# Amplifier_Mixer.net
KiCad netlist of a schematic drawn in EAGLE
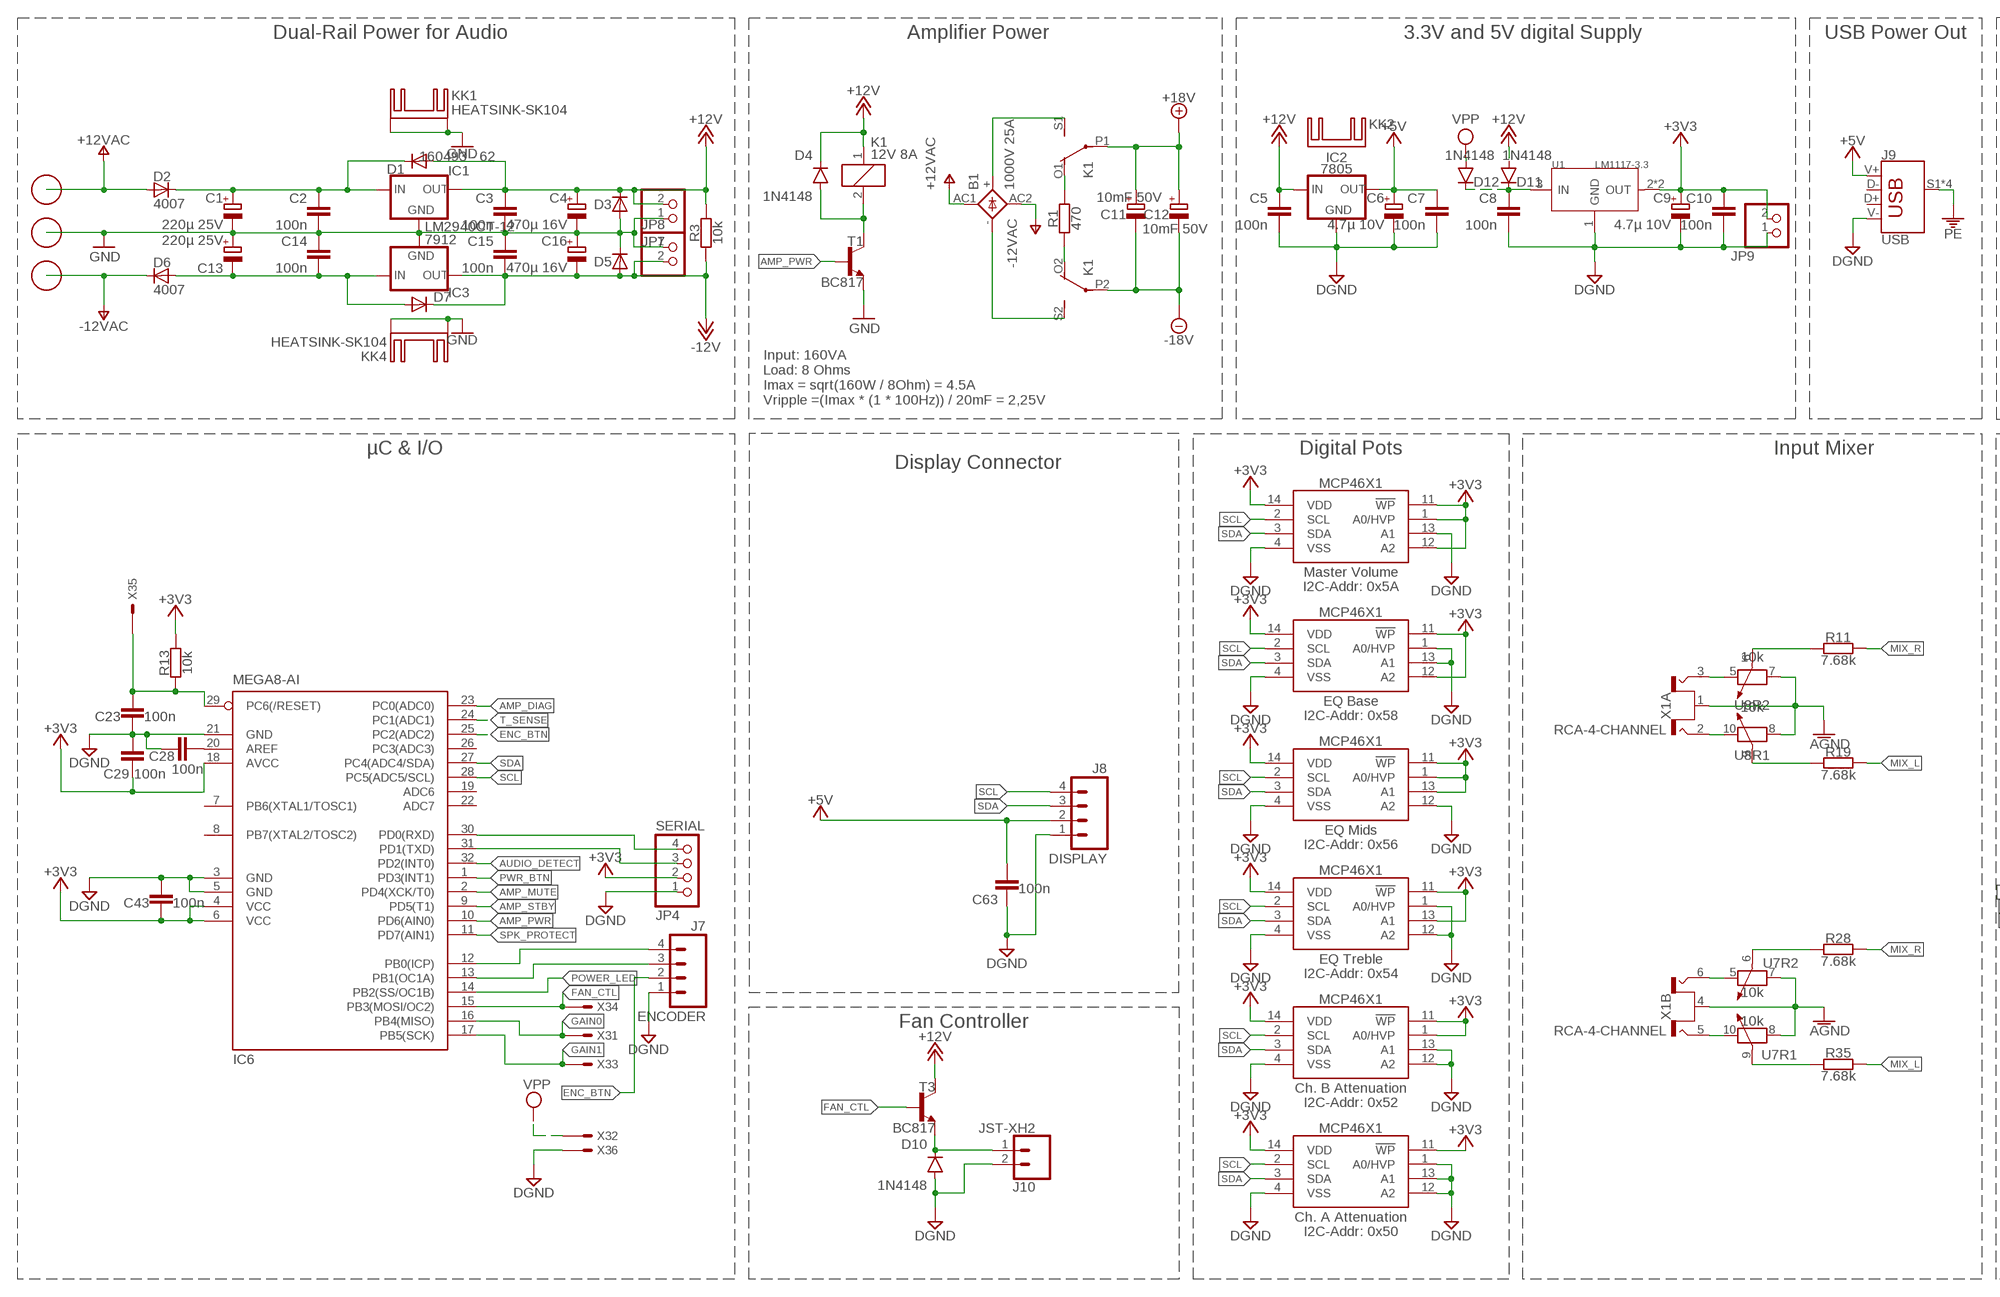
[diagram p0: schematic, sheet 1, part 1 of 2]
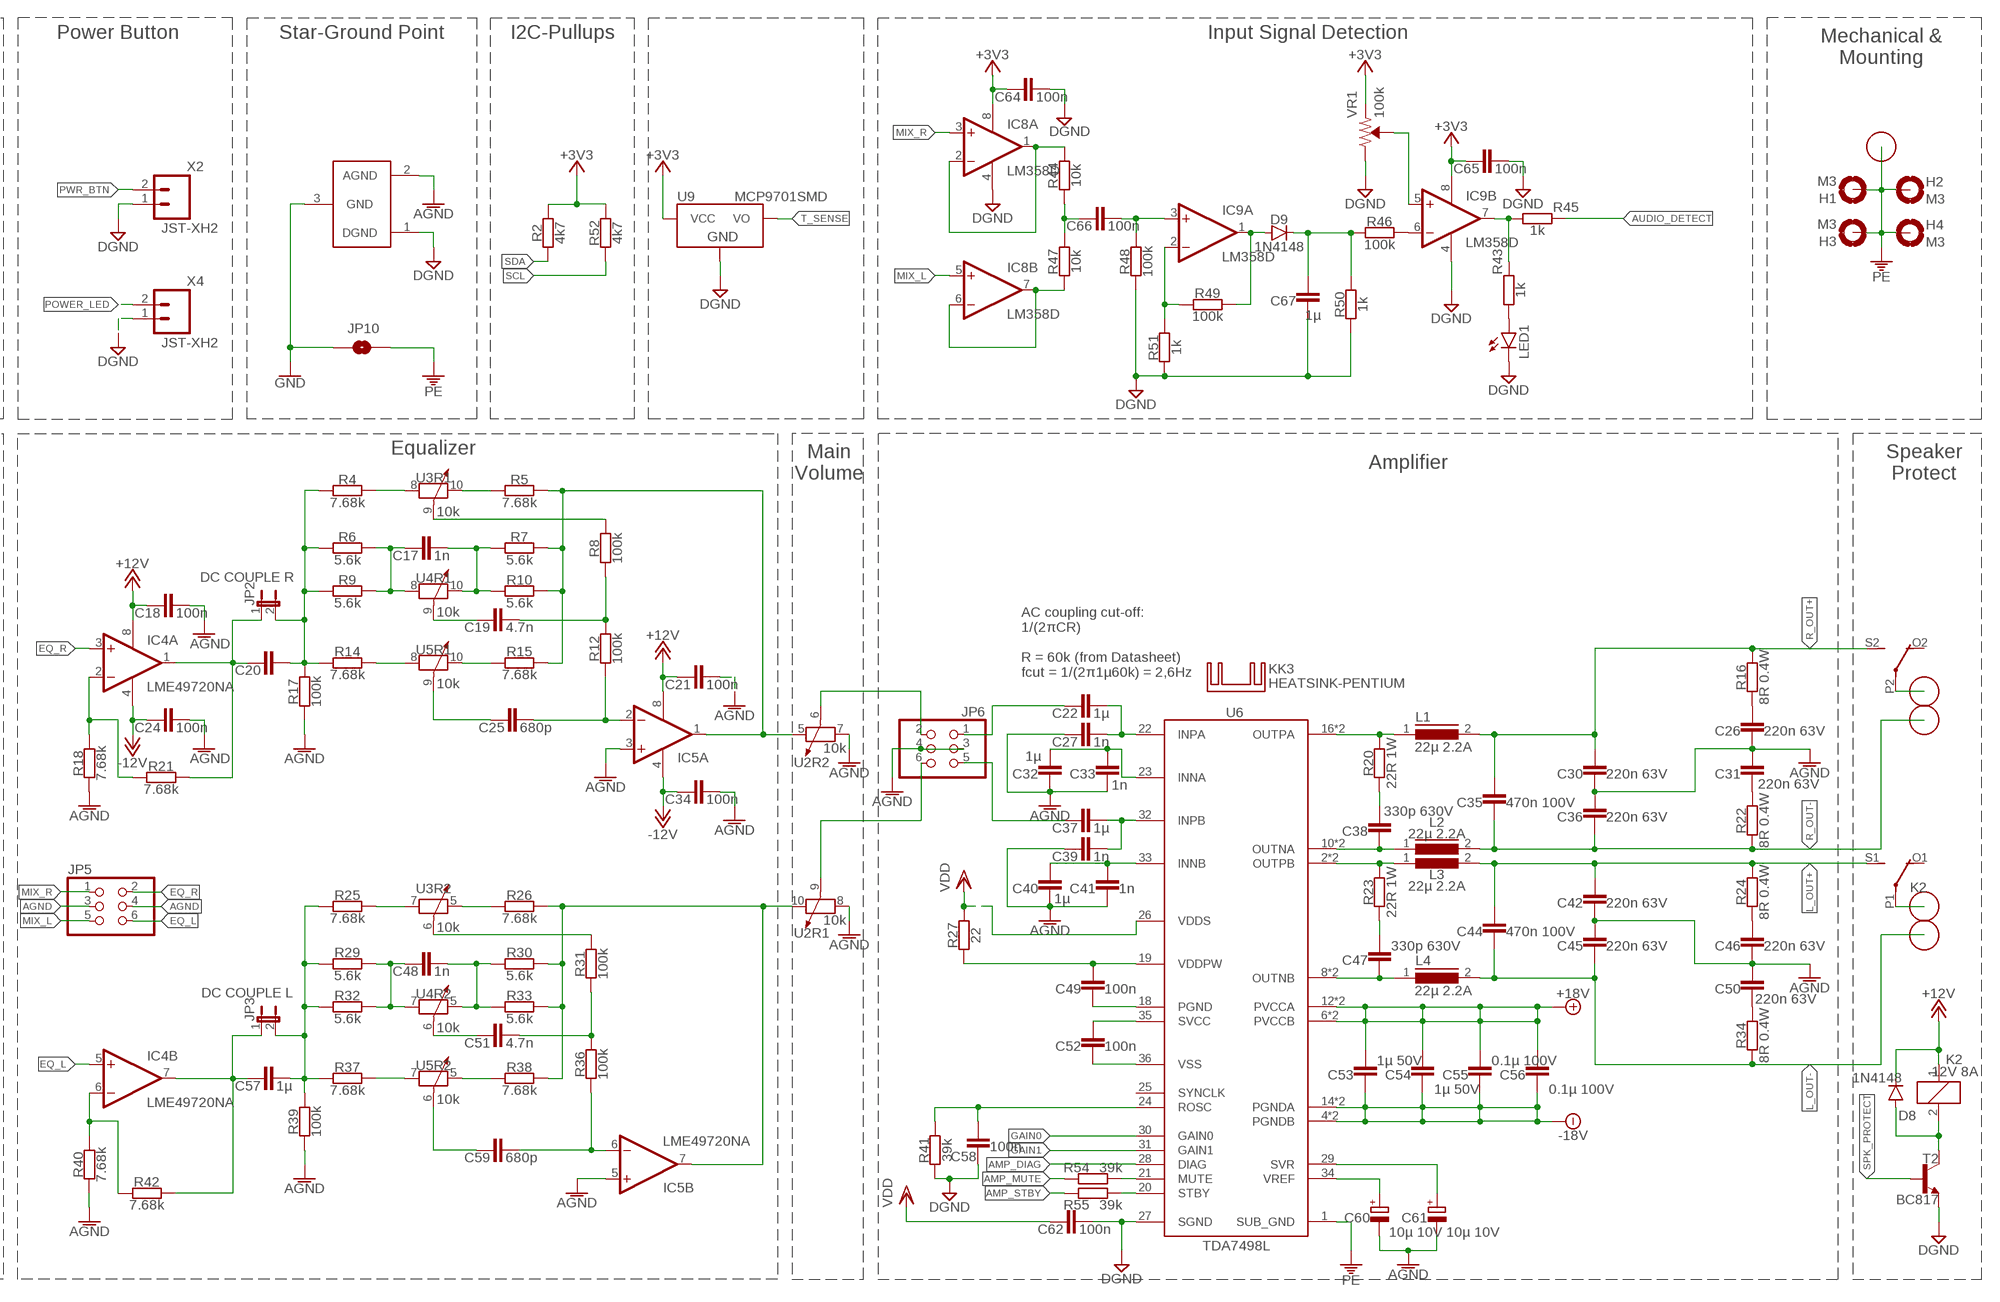
[diagram p1: schematic, sheet 1, part 2 of 2]

(export (version "E")
  (design (tool "Eeschema 10.0.6"))
  (components
    (comp (ref "B1")
      (value "1000V 25A")
      (footprint "eagle-import:FB100")
      (libsource (lib "eagle-import") (part "RECTIFIER-FB100"))
    )
    (comp (ref "C1")
      (value "220µ 25V")
      (footprint "eagle-import:175TMP-0810")
      (libsource (lib "eagle-import") (part "CPOL-EU175TMP-0810"))
    )
    (comp (ref "C2")
      (value "100n")
      (footprint "eagle-import:C0603")
      (libsource (lib "eagle-import") (part "C-EUC0603"))
    )
    (comp (ref "C3")
      (value "100n")
      (footprint "eagle-import:C0603")
      (libsource (lib "eagle-import") (part "C-EUC0603"))
    )
    (comp (ref "C4")
      (value "470µ 16V")
      (footprint "eagle-import:175TMP-0810")
      (libsource (lib "eagle-import") (part "CPOL-EU175TMP-0810"))
    )
    (comp (ref "C5")
      (value "100n")
      (footprint "eagle-import:C0603")
      (libsource (lib "eagle-import") (part "C-EUC0603"))
    )
    (comp (ref "C6")
      (value "4.7µ 10V")
      (footprint "eagle-import:153CLV-0505")
      (libsource (lib "eagle-import") (part "CPOL-EU153CLV-0505"))
    )
    (comp (ref "C7")
      (value "100n")
      (footprint "eagle-import:C0603")
      (libsource (lib "eagle-import") (part "C-EUC0603"))
    )
    (comp (ref "C8")
      (value "100n")
      (footprint "eagle-import:C0603")
      (libsource (lib "eagle-import") (part "C-EUC0603"))
    )
    (comp (ref "C9")
      (value "4.7µ 10V")
      (footprint "eagle-import:153CLV-0505")
      (libsource (lib "eagle-import") (part "CPOL-EU153CLV-0505"))
    )
    (comp (ref "C10")
      (value "100n")
      (footprint "eagle-import:C0603")
      (libsource (lib "eagle-import") (part "C-EUC0603"))
    )
    (comp (ref "C11")
      (value "10mF 50V")
      (footprint "eagle-import:EB35D")
      (libsource (lib "eagle-import") (part "TEAPO-SLG109M050S1A5T"))
    )
    (comp (ref "C12")
      (value "10mF 50V")
      (footprint "eagle-import:EB35D")
      (libsource (lib "eagle-import") (part "TEAPO-SLG109M050S1A5T"))
    )
    (comp (ref "C13")
      (value "220µ 25V")
      (footprint "eagle-import:175TMP-0810")
      (libsource (lib "eagle-import") (part "CPOL-EU175TMP-0810"))
    )
    (comp (ref "C14")
      (value "100n")
      (footprint "eagle-import:C0603")
      (libsource (lib "eagle-import") (part "C-EUC0603"))
    )
    (comp (ref "C15")
      (value "100n")
      (footprint "eagle-import:C0603")
      (libsource (lib "eagle-import") (part "C-EUC0603"))
    )
    (comp (ref "C16")
      (value "470µ 16V")
      (footprint "eagle-import:175TMP-0810")
      (libsource (lib "eagle-import") (part "CPOL-EU175TMP-0810"))
    )
    (comp (ref "C17")
      (value "1n")
      (footprint "eagle-import:C050-025X075")
      (libsource (lib "eagle-import") (part "C-EU050-025X075"))
    )
    (comp (ref "C18")
      (value "100n")
      (footprint "eagle-import:C0603")
      (libsource (lib "eagle-import") (part "C-EUC0603"))
    )
    (comp (ref "C19")
      (value "4.7n")
      (footprint "eagle-import:C075-032X103")
      (libsource (lib "eagle-import") (part "C-EU075-032X103"))
    )
    (comp (ref "C20")
      (value "DC COUPLE L")
      (footprint "eagle-import:C050-050X075")
      (libsource (lib "eagle-import") (part "C-EU050-050X075"))
    )
    (comp (ref "C21")
      (value "100n")
      (footprint "eagle-import:C0603")
      (libsource (lib "eagle-import") (part "C-EUC0603"))
    )
    (comp (ref "C22")
      (value "1µ")
      (footprint "eagle-import:C050-050X075")
      (libsource (lib "eagle-import") (part "C-EU050-050X075"))
    )
    (comp (ref "C23")
      (value "100n")
      (footprint "eagle-import:C0603")
      (libsource (lib "eagle-import") (part "C-EUC0603"))
    )
    (comp (ref "C24")
      (value "100n")
      (footprint "eagle-import:C0603")
      (libsource (lib "eagle-import") (part "C-EUC0603"))
    )
    (comp (ref "C25")
      (value "680p")
      (footprint "eagle-import:C050-045X075")
      (libsource (lib "eagle-import") (part "C-EU050-045X075"))
    )
    (comp (ref "C26")
      (value "220n 63V")
      (footprint "eagle-import:C050-025X075")
      (libsource (lib "eagle-import") (part "C-EU050-025X075"))
    )
    (comp (ref "C27")
      (value "1n")
      (footprint "eagle-import:C050-025X075")
      (libsource (lib "eagle-import") (part "C-EU050-025X075"))
    )
    (comp (ref "C28")
      (value "100n")
      (footprint "eagle-import:C0603")
      (libsource (lib "eagle-import") (part "C-EUC0603"))
    )
    (comp (ref "C29")
      (value "100n")
      (footprint "eagle-import:C0603")
      (libsource (lib "eagle-import") (part "C-EUC0603"))
    )
    (comp (ref "C30")
      (value "220n 63V")
      (footprint "eagle-import:C050-025X075")
      (libsource (lib "eagle-import") (part "C-EU050-025X075"))
    )
    (comp (ref "C31")
      (value "220n 63V")
      (footprint "eagle-import:C050-025X075")
      (libsource (lib "eagle-import") (part "C-EU050-025X075"))
    )
    (comp (ref "C32")
      (value "1µ")
      (footprint "eagle-import:C050-050X075")
      (libsource (lib "eagle-import") (part "C-EU050-050X075"))
    )
    (comp (ref "C33")
      (value "1n")
      (footprint "eagle-import:C050-025X075")
      (libsource (lib "eagle-import") (part "C-EU050-025X075"))
    )
    (comp (ref "C34")
      (value "100n")
      (footprint "eagle-import:C0603")
      (libsource (lib "eagle-import") (part "C-EUC0603"))
    )
    (comp (ref "C35")
      (value "470n 100V")
      (footprint "eagle-import:C050-045X075")
      (libsource (lib "eagle-import") (part "C-EU050-045X075"))
    )
    (comp (ref "C36")
      (value "220n 63V")
      (footprint "eagle-import:C050-025X075")
      (libsource (lib "eagle-import") (part "C-EU050-025X075"))
    )
    (comp (ref "C37")
      (value "1µ")
      (footprint "eagle-import:C050-050X075")
      (libsource (lib "eagle-import") (part "C-EU050-050X075"))
    )
    (comp (ref "C38")
      (value "330p 630V")
      (footprint "eagle-import:C050-045X075")
      (libsource (lib "eagle-import") (part "C-EU050-045X075"))
    )
    (comp (ref "C39")
      (value "1n")
      (footprint "eagle-import:C050-025X075")
      (libsource (lib "eagle-import") (part "C-EU050-025X075"))
    )
    (comp (ref "C40")
      (value "1µ")
      (footprint "eagle-import:C050-050X075")
      (libsource (lib "eagle-import") (part "C-EU050-050X075"))
    )
    (comp (ref "C41")
      (value "1n")
      (footprint "eagle-import:C050-025X075")
      (libsource (lib "eagle-import") (part "C-EU050-025X075"))
    )
    (comp (ref "C42")
      (value "220n 63V")
      (footprint "eagle-import:C050-025X075")
      (libsource (lib "eagle-import") (part "C-EU050-025X075"))
    )
    (comp (ref "C43")
      (value "100n")
      (footprint "eagle-import:C0603")
      (libsource (lib "eagle-import") (part "C-EUC0603"))
    )
    (comp (ref "C44")
      (value "470n 100V")
      (footprint "eagle-import:C050-045X075")
      (libsource (lib "eagle-import") (part "C-EU050-045X075"))
    )
    (comp (ref "C45")
      (value "220n 63V")
      (footprint "eagle-import:C050-025X075")
      (libsource (lib "eagle-import") (part "C-EU050-025X075"))
    )
    (comp (ref "C46")
      (value "220n 63V")
      (footprint "eagle-import:C050-025X075")
      (libsource (lib "eagle-import") (part "C-EU050-025X075"))
    )
    (comp (ref "C47")
      (value "330p 630V")
      (footprint "eagle-import:C050-045X075")
      (libsource (lib "eagle-import") (part "C-EU050-045X075"))
    )
    (comp (ref "C48")
      (value "1n")
      (footprint "eagle-import:C050-025X075")
      (libsource (lib "eagle-import") (part "C-EU050-025X075"))
    )
    (comp (ref "C49")
      (value "100n")
      (footprint "eagle-import:C0603")
      (libsource (lib "eagle-import") (part "C-EUC0603"))
    )
    (comp (ref "C50")
      (value "220n 63V")
      (footprint "eagle-import:C050-025X075")
      (libsource (lib "eagle-import") (part "C-EU050-025X075"))
    )
    (comp (ref "C51")
      (value "4.7n")
      (footprint "eagle-import:C075-032X103")
      (libsource (lib "eagle-import") (part "C-EU075-032X103"))
    )
    (comp (ref "C52")
      (value "100n")
      (footprint "eagle-import:C0603")
      (libsource (lib "eagle-import") (part "C-EUC0603"))
    )
    (comp (ref "C53")
      (value "1µ 50V")
      (footprint "eagle-import:C1206K")
      (fields (field (name "SPICEPREFIX") "Kemet C1206C105K5RAC7800+"))
      (libsource (lib "eagle-import") (part "C-EUC1206K"))
    )
    (comp (ref "C54")
      (value "1µ 50V")
      (footprint "eagle-import:C1206K")
      (fields (field (name "SPICEPREFIX") "Kemet C1206C105K5RAC7800+"))
      (libsource (lib "eagle-import") (part "C-EUC1206K"))
    )
    (comp (ref "C55")
      (value "0.1µ 100V")
      (footprint "eagle-import:C1206K")
      (fields (field (name "SPICEPREFIX") "Kemet C1206C104K1RAC7800+"))
      (libsource (lib "eagle-import") (part "C-EUC1206K"))
    )
    (comp (ref "C56")
      (value "0.1µ 100V")
      (footprint "eagle-import:C1206K")
      (fields (field (name "SPICEPREFIX") "Kemet C1206C104K1RAC7800+"))
      (libsource (lib "eagle-import") (part "C-EUC1206K"))
    )
    (comp (ref "C57")
      (value "1µ")
      (footprint "eagle-import:C050-050X075")
      (libsource (lib "eagle-import") (part "C-EU050-050X075"))
    )
    (comp (ref "C58")
      (value "100n")
      (footprint "eagle-import:C0603")
      (libsource (lib "eagle-import") (part "C-EUC0603"))
    )
    (comp (ref "C59")
      (value "680p")
      (footprint "eagle-import:C050-045X075")
      (libsource (lib "eagle-import") (part "C-EU050-045X075"))
    )
    (comp (ref "C60")
      (value "10µ 10V")
      (footprint "eagle-import:153CLV-0505")
      (libsource (lib "eagle-import") (part "CPOL-EU153CLV-0505"))
    )
    (comp (ref "C61")
      (value "10µ 10V")
      (footprint "eagle-import:153CLV-0505")
      (libsource (lib "eagle-import") (part "CPOL-EU153CLV-0505"))
    )
    (comp (ref "C62")
      (value "100n")
      (footprint "eagle-import:C0603")
      (libsource (lib "eagle-import") (part "C-EUC0603"))
    )
    (comp (ref "C63")
      (value "100n")
      (footprint "eagle-import:C0603")
      (libsource (lib "eagle-import") (part "C-EUC0603"))
    )
    (comp (ref "C64")
      (value "100n")
      (footprint "eagle-import:C0603")
      (libsource (lib "eagle-import") (part "C-EUC0603"))
    )
    (comp (ref "C65")
      (value "100n")
      (footprint "eagle-import:C0603")
      (libsource (lib "eagle-import") (part "C-EUC0603"))
    )
    (comp (ref "C66")
      (value "100n")
      (footprint "eagle-import:C0603")
      (libsource (lib "eagle-import") (part "C-EUC0603"))
    )
    (comp (ref "C67")
      (value "1µ")
      (footprint "eagle-import:C0603")
      (libsource (lib "eagle-import") (part "C-EUC0603"))
    )
    (comp (ref "D1")
      (value "4007")
      (footprint "eagle-import:SODFL5024X231")
      (fields (field (name "CONRAD") "160493 - 62"))
      (libsource (lib "eagle-import") (part "DIODE"))
    )
    (comp (ref "D2")
      (value "4007")
      (footprint "eagle-import:SODFL5024X231")
      (libsource (lib "eagle-import") (part "DIODE"))
    )
    (comp (ref "D3")
      (value "4007")
      (footprint "eagle-import:SODFL5024X231")
      (libsource (lib "eagle-import") (part "DIODE"))
    )
    (comp (ref "D4")
      (value "1N4148")
      (footprint "eagle-import:SOD-323")
      (libsource (lib "eagle-import") (part "DIODEBAS16"))
    )
    (comp (ref "D5")
      (value "4007")
      (footprint "eagle-import:SODFL5024X231")
      (libsource (lib "eagle-import") (part "DIODE"))
    )
    (comp (ref "D6")
      (value "4007")
      (footprint "eagle-import:SODFL5024X231")
      (libsource (lib "eagle-import") (part "DIODE"))
    )
    (comp (ref "D7")
      (value "4007")
      (footprint "eagle-import:SODFL5024X231")
      (libsource (lib "eagle-import") (part "DIODE"))
    )
    (comp (ref "D8")
      (value "1N4148")
      (footprint "eagle-import:SOD-323")
      (libsource (lib "eagle-import") (part "DIODEBAS16"))
    )
    (comp (ref "D9")
      (value "1N4148")
      (footprint "eagle-import:SOD-323")
      (libsource (lib "eagle-import") (part "DIODEBAS16"))
    )
    (comp (ref "D10")
      (value "1N4148")
      (footprint "eagle-import:SOD-323")
      (libsource (lib "eagle-import") (part "DIODEBAS16"))
    )
    (comp (ref "D11")
      (value "1N4148")
      (footprint "eagle-import:SOD-323")
      (libsource (lib "eagle-import") (part "DIODEBAS16"))
    )
    (comp (ref "D12")
      (value "1N4148")
      (footprint "eagle-import:SOD-323")
      (libsource (lib "eagle-import") (part "DIODEBAS16"))
    )
    (comp (ref "H1")
      (value "M3")
      (footprint "eagle-import:3,0-PAD")
      (libsource (lib "eagle-import") (part "HOLE-3MM-PAD"))
    )
    (comp (ref "H2")
      (value "M3")
      (footprint "eagle-import:3,0-PAD")
      (libsource (lib "eagle-import") (part "HOLE-3MM-PAD"))
    )
    (comp (ref "H3")
      (value "M3")
      (footprint "eagle-import:3,0-PAD")
      (libsource (lib "eagle-import") (part "HOLE-3MM-PAD"))
    )
    (comp (ref "H4")
      (value "M3")
      (footprint "eagle-import:3,0-PAD")
      (libsource (lib "eagle-import") (part "HOLE-3MM-PAD"))
    )
    (comp (ref "IC1")
      (value "LM2940CT-12")
      (footprint "eagle-import:78XXS")
      (libsource (lib "eagle-import") (part "78XXS"))
    )
    (comp (ref "IC2")
      (value "7805")
      (footprint "eagle-import:78XXS")
      (libsource (lib "eagle-import") (part "78XXS"))
    )
    (comp (ref "IC3")
      (value "7912")
      (footprint "eagle-import:79XXS")
      (libsource (lib "eagle-import") (part "79XXS"))
    )
    (comp (ref "IC4")
      (value "LME49720NA")
      (footprint "eagle-import:DIL08")
      (fields (field (name "CONRAD") "1010937 - 62") (field (name "STOCK") "0"))
      (libsource (lib "eagle-import") (part "LM358N"))
    )
    (comp (ref "IC5")
      (value "LME49720NA")
      (footprint "eagle-import:DIL08")
      (fields (field (name "CONRAD") "1010937 - 62") (field (name "STOCK") "0"))
      (libsource (lib "eagle-import") (part "LM358N"))
    )
    (comp (ref "IC6")
      (value "MEGA8-AI")
      (footprint "eagle-import:TQFP32-08")
      (fields (field (name "MPN") "ATMEGA8-16AU"))
      (libsource (lib "eagle-import") (part "MEGA8-AI"))
    )
    (comp (ref "IC8")
      (value "LM358D")
      (footprint "eagle-import:SO08")
      (fields
        (field (name "CONRAD") "1010764 - 62")
        (field (name "MOUSER") "511-LM358DT")
        (field (name "STOCK") "2")
      )
      (libsource (lib "eagle-import") (part "2AMP_P8+4D"))
    )
    (comp (ref "IC9")
      (value "LM358D")
      (footprint "eagle-import:SO08")
      (fields
        (field (name "CONRAD") "1010764 - 62")
        (field (name "MOUSER") "511-LM358DT")
        (field (name "STOCK") "2")
      )
      (libsource (lib "eagle-import") (part "2AMP_P8+4D"))
    )
    (comp (ref "J1")
      (value "6MM")
      (footprint "eagle-import:TE-726386")
      (libsource (lib "eagle-import") (part "TERMINAL-1"))
    )
    (comp (ref "J2")
      (value "6MM")
      (footprint "eagle-import:TE-726386")
      (libsource (lib "eagle-import") (part "TERMINAL-1"))
    )
    (comp (ref "J3")
      (value "6MM")
      (footprint "eagle-import:TE-726386")
      (libsource (lib "eagle-import") (part "TERMINAL-1"))
    )
    (comp (ref "J4")
      (value "6MM")
      (footprint "eagle-import:TE-726386")
      (libsource (lib "eagle-import") (part "TERMINAL-1"))
    )
    (comp (ref "J5")
      (value "TERMINAL-BLOCK-2PLUG-IN")
      (footprint "eagle-import:MSTBV2")
      (fields
        (field (name "CONRAD") "1327203 - 62")
        (field (name "MOUSER") "651-1954919")
        (field (name "STOCK") "2")
      )
      (libsource (lib "eagle-import") (part "TERMINAL-BLOCK-2PLUG-IN"))
    )
    (comp (ref "J6")
      (value "TERMINAL-BLOCK-2PLUG-IN")
      (footprint "eagle-import:MSTBV2")
      (fields
        (field (name "CONRAD") "1327203 - 62")
        (field (name "MOUSER") "651-1954919")
        (field (name "STOCK") "2")
      )
      (libsource (lib "eagle-import") (part "TERMINAL-BLOCK-2PLUG-IN"))
    )
    (comp (ref "J7")
      (value "ENCODER")
      (footprint "eagle-import:JST-4-PTH-VERT")
      (libsource (lib "eagle-import") (part "JST-XH4"))
    )
    (comp (ref "J8")
      (value "DISPLAY")
      (footprint "eagle-import:JST-4-PTH-VERT")
      (libsource (lib "eagle-import") (part "JST-XH4"))
    )
    (comp (ref "J9")
      (value "USB")
      (footprint "eagle-import:ECON-USBBUVA")
      (libsource (lib "eagle-import") (part "USB"))
    )
    (comp (ref "J10")
      (value "JST-XH2")
      (footprint "eagle-import:JST-2-PTH-VERT")
      (libsource (lib "eagle-import") (part "JST-XH2"))
    )
    (comp (ref "JP1")
      (value "GND_CONNECT")
      (footprint "eagle-import:GND_CONNECT")
      (libsource (lib "eagle-import") (part "GND_CONNECT"))
    )
    (comp (ref "JP2")
      (value "DC COULE R")
      (footprint "eagle-import:JP1")
      (libsource (lib "eagle-import") (part "JP1E"))
    )
    (comp (ref "JP3")
      (value "DC COUPLE L")
      (footprint "eagle-import:JP1")
      (libsource (lib "eagle-import") (part "JP1E"))
    )
    (comp (ref "JP4")
      (value "SERIAL")
      (footprint "eagle-import:1X04")
      (libsource (lib "eagle-import") (part "PINHD-1X4"))
    )
    (comp (ref "JP5")
      (value "MIX OUT")
      (footprint "eagle-import:2X03")
      (libsource (lib "eagle-import") (part "PINHD-2X3"))
    )
    (comp (ref "JP6")
      (value "PREAMP OUT")
      (footprint "eagle-import:2X03")
      (libsource (lib "eagle-import") (part "PINHD-2X3"))
    )
    (comp (ref "JP7")
      (value "PINHD-1X2")
      (footprint "eagle-import:1X02")
      (libsource (lib "eagle-import") (part "PINHD-1X2"))
    )
    (comp (ref "JP8")
      (value "PINHD-1X2")
      (footprint "eagle-import:1X02")
      (libsource (lib "eagle-import") (part "PINHD-1X2"))
    )
    (comp (ref "JP9")
      (value "PINHD-1X2")
      (footprint "eagle-import:1X02")
      (libsource (lib "eagle-import") (part "PINHD-1X2"))
    )
    (comp (ref "JP10")
      (value "PEGND")
      (footprint "eagle-import:SMT-JUMPER_2_NO_NO-SILK")
      (libsource (lib "eagle-import") (part "JUMPER-SMT_2_NO_NO-SILK"))
    )
    (comp (ref "K1")
      (value "12V 8A")
      (footprint "eagle-import:F4052")
      (fields
        (field (name "CONRAD") "629528 - 62")
        (field (name "MOUSER") "655-RT424012")
        (field (name "SPEC") "Hongfa HF115F/012-2ZS4A")
        (field (name "STOCK") "0")
      )
      (libsource (lib "eagle-import") (part "RELAY-F40.52"))
    )
    (comp (ref "K2")
      (value "12V 8A")
      (footprint "eagle-import:F4052")
      (fields
        (field (name "CONRAD") "629528 - 62")
        (field (name "SPEC") "Hongfa HF115F/012-2ZS4A")
        (field (name "MOUSER") "655-RT424012")
        (field (name "STOCK") "0")
      )
      (libsource (lib "eagle-import") (part "RELAY-F40.52"))
    )
    (comp (ref "KK1")
      (value "HEATSINK-SK104")
      (footprint "eagle-import:SK104-PAD")
      (libsource (lib "eagle-import") (part "HEATSINK-SK104"))
    )
    (comp (ref "KK2")
      (value "HEATSINK-SK95")
      (footprint "eagle-import:SK95-2M3")
      (libsource (lib "eagle-import") (part "HEATSINK-SK95"))
    )
    (comp (ref "KK3")
      (value "HEATSINK-PENTIUM")
      (footprint "eagle-import:HEATSINK-PENTIUM")
      (libsource (lib "eagle-import") (part "HEATSINK-PENTIUM"))
    )
    (comp (ref "KK4")
      (value "HEATSINK-SK104")
      (footprint "eagle-import:SK104-PAD")
      (libsource (lib "eagle-import") (part "HEATSINK-SK104"))
    )
    (comp (ref "L1")
      (value "22µ 2.2A")
      (footprint "eagle-import:INDUCTOR-12MM")
      (libsource (lib "eagle-import") (part "INDUCTOR12MM-SMD"))
    )
    (comp (ref "L2")
      (value "22µ 2.2A")
      (footprint "eagle-import:INDUCTOR-12MM")
      (libsource (lib "eagle-import") (part "INDUCTOR12MM-SMD"))
    )
    (comp (ref "L3")
      (value "22µ 2.2A")
      (footprint "eagle-import:INDUCTOR-12MM")
      (libsource (lib "eagle-import") (part "INDUCTOR12MM-SMD"))
    )
    (comp (ref "L4")
      (value "22µ 2.2A")
      (footprint "eagle-import:INDUCTOR-12MM")
      (libsource (lib "eagle-import") (part "INDUCTOR12MM-SMD"))
    )
    (comp (ref "LED1")
      (value "LEDCHIP-LED0603")
      (footprint "eagle-import:CHIP-LED0603")
      (libsource (lib "eagle-import") (part "LEDCHIP-LED0603"))
    )
    (comp (ref "R1")
      (value "470")
      (footprint "eagle-import:0617_22")
      (libsource (lib "eagle-import") (part "RESISTOR-0617-22"))
    )
    (comp (ref "R2")
      (value "4k7")
      (footprint "eagle-import:R0603")
      (libsource (lib "eagle-import") (part "R-EU_R0603"))
    )
    (comp (ref "R3")
      (value "10k")
      (footprint "eagle-import:R0603")
      (libsource (lib "eagle-import") (part "R-EU_R0603"))
    )
    (comp (ref "R4")
      (value "7.68k")
      (footprint "eagle-import:MINI_MELF-0207W")
      (libsource (lib "eagle-import") (part "R-EU_MELF0207W"))
    )
    (comp (ref "R5")
      (value "7.68k")
      (footprint "eagle-import:MINI_MELF-0207W")
      (libsource (lib "eagle-import") (part "R-EU_MELF0207W"))
    )
    (comp (ref "R6")
      (value "5.6k")
      (footprint "eagle-import:MINI_MELF-0207W")
      (libsource (lib "eagle-import") (part "R-EU_MELF0207W"))
    )
    (comp (ref "R7")
      (value "5.6k")
      (footprint "eagle-import:MINI_MELF-0207W")
      (libsource (lib "eagle-import") (part "R-EU_MELF0207W"))
    )
    (comp (ref "R8")
      (value "100k")
      (footprint "eagle-import:MINI_MELF-0204W")
      (libsource (lib "eagle-import") (part "R-EU_MELF0204W"))
    )
    (comp (ref "R9")
      (value "5.6k")
      (footprint "eagle-import:MINI_MELF-0207W")
      (libsource (lib "eagle-import") (part "R-EU_MELF0207W"))
    )
    (comp (ref "R10")
      (value "5.6k")
      (footprint "eagle-import:MINI_MELF-0207W")
      (libsource (lib "eagle-import") (part "R-EU_MELF0207W"))
    )
    (comp (ref "R11")
      (value "7.68k")
      (footprint "eagle-import:MINI_MELF-0207W")
      (libsource (lib "eagle-import") (part "R-EU_MELF0207W"))
    )
    (comp (ref "R12")
      (value "100k")
      (footprint "eagle-import:MINI_MELF-0204W")
      (libsource (lib "eagle-import") (part "R-EU_MELF0204W"))
    )
    (comp (ref "R13")
      (value "10k")
      (footprint "eagle-import:R0603")
      (libsource (lib "eagle-import") (part "R-EU_R0603"))
    )
    (comp (ref "R14")
      (value "7.68k")
      (footprint "eagle-import:MINI_MELF-0207W")
      (libsource (lib "eagle-import") (part "R-EU_MELF0207W"))
    )
    (comp (ref "R15")
      (value "7.68k")
      (footprint "eagle-import:MINI_MELF-0207W")
      (libsource (lib "eagle-import") (part "R-EU_MELF0207W"))
    )
    (comp (ref "R16")
      (value "8R 0.4W")
      (footprint "eagle-import:MINI_MELF-0204W")
      (libsource (lib "eagle-import") (part "R-EU_MELF0204W"))
    )
    (comp (ref "R17")
      (value "100k")
      (footprint "eagle-import:MINI_MELF-0204W")
      (libsource (lib "eagle-import") (part "R-EU_MELF0204W"))
    )
    (comp (ref "R18")
      (value "7.68k")
      (footprint "eagle-import:MINI_MELF-0207W")
      (libsource (lib "eagle-import") (part "R-EU_MELF0207W"))
    )
    (comp (ref "R19")
      (value "7.68k")
      (footprint "eagle-import:MINI_MELF-0207W")
      (libsource (lib "eagle-import") (part "R-EU_MELF0207W"))
    )
    (comp (ref "R20")
      (value "22R 1W")
      (footprint "eagle-import:MINI_MELF-0207W")
      (libsource (lib "eagle-import") (part "R-EU_MELF0207W"))
    )
    (comp (ref "R21")
      (value "7.68k")
      (footprint "eagle-import:MINI_MELF-0207W")
      (libsource (lib "eagle-import") (part "R-EU_MELF0207W"))
    )
    (comp (ref "R22")
      (value "8R 0.4W")
      (footprint "eagle-import:MINI_MELF-0204W")
      (libsource (lib "eagle-import") (part "R-EU_MELF0204W"))
    )
    (comp (ref "R23")
      (value "22R 1W")
      (footprint "eagle-import:MINI_MELF-0207W")
      (libsource (lib "eagle-import") (part "R-EU_MELF0207W"))
    )
    (comp (ref "R24")
      (value "8R 0.4W")
      (footprint "eagle-import:MINI_MELF-0204W")
      (libsource (lib "eagle-import") (part "R-EU_MELF0204W"))
    )
    (comp (ref "R25")
      (value "7.68k")
      (footprint "eagle-import:MINI_MELF-0207W")
      (libsource (lib "eagle-import") (part "R-EU_MELF0207W"))
    )
    (comp (ref "R26")
      (value "7.68k")
      (footprint "eagle-import:MINI_MELF-0207W")
      (libsource (lib "eagle-import") (part "R-EU_MELF0207W"))
    )
    (comp (ref "R27")
      (value "22")
      (footprint "eagle-import:R0603")
      (libsource (lib "eagle-import") (part "R-EU_R0603"))
    )
    (comp (ref "R28")
      (value "7.68k")
      (footprint "eagle-import:MINI_MELF-0207W")
      (libsource (lib "eagle-import") (part "R-EU_MELF0207W"))
    )
    (comp (ref "R29")
      (value "5.6k")
      (footprint "eagle-import:MINI_MELF-0207W")
      (libsource (lib "eagle-import") (part "R-EU_MELF0207W"))
    )
    (comp (ref "R30")
      (value "5.6k")
      (footprint "eagle-import:MINI_MELF-0207W")
      (libsource (lib "eagle-import") (part "R-EU_MELF0207W"))
    )
    (comp (ref "R31")
      (value "100k")
      (footprint "eagle-import:MINI_MELF-0204W")
      (libsource (lib "eagle-import") (part "R-EU_MELF0204W"))
    )
    (comp (ref "R32")
      (value "5.6k")
      (footprint "eagle-import:MINI_MELF-0207W")
      (libsource (lib "eagle-import") (part "R-EU_MELF0207W"))
    )
    (comp (ref "R33")
      (value "5.6k")
      (footprint "eagle-import:MINI_MELF-0207W")
      (libsource (lib "eagle-import") (part "R-EU_MELF0207W"))
    )
    (comp (ref "R34")
      (value "8R 0.4W")
      (footprint "eagle-import:MINI_MELF-0204W")
      (libsource (lib "eagle-import") (part "R-EU_MELF0204W"))
    )
    (comp (ref "R35")
      (value "7.68k")
      (footprint "eagle-import:MINI_MELF-0207W")
      (libsource (lib "eagle-import") (part "R-EU_MELF0207W"))
    )
    (comp (ref "R36")
      (value "100k")
      (footprint "eagle-import:MINI_MELF-0204W")
      (libsource (lib "eagle-import") (part "R-EU_MELF0204W"))
    )
    (comp (ref "R37")
      (value "7.68k")
      (footprint "eagle-import:MINI_MELF-0207W")
      (libsource (lib "eagle-import") (part "R-EU_MELF0207W"))
    )
    (comp (ref "R38")
      (value "7.68k")
      (footprint "eagle-import:MINI_MELF-0207W")
      (libsource (lib "eagle-import") (part "R-EU_MELF0207W"))
    )
    (comp (ref "R39")
      (value "100k")
      (footprint "eagle-import:MINI_MELF-0204W")
      (libsource (lib "eagle-import") (part "R-EU_MELF0204W"))
    )
    (comp (ref "R40")
      (value "7.68k")
      (footprint "eagle-import:MINI_MELF-0207W")
      (libsource (lib "eagle-import") (part "R-EU_MELF0207W"))
    )
    (comp (ref "R41")
      (value "39k")
      (footprint "eagle-import:R0603")
      (libsource (lib "eagle-import") (part "R-EU_R0603"))
    )
    (comp (ref "R42")
      (value "7.68k")
      (footprint "eagle-import:MINI_MELF-0207W")
      (libsource (lib "eagle-import") (part "R-EU_MELF0207W"))
    )
    (comp (ref "R43")
      (value "1k")
      (footprint "eagle-import:R0603")
      (libsource (lib "eagle-import") (part "R-EU_R0603"))
    )
    (comp (ref "R44")
      (value "10k")
      (footprint "eagle-import:R0603")
      (libsource (lib "eagle-import") (part "R-EU_R0603"))
    )
    (comp (ref "R45")
      (value "1k")
      (footprint "eagle-import:R0603")
      (libsource (lib "eagle-import") (part "R-EU_R0603"))
    )
    (comp (ref "R46")
      (value "100k")
      (footprint "eagle-import:R0603")
      (libsource (lib "eagle-import") (part "R-EU_R0603"))
    )
    (comp (ref "R47")
      (value "10k")
      (footprint "eagle-import:R0603")
      (libsource (lib "eagle-import") (part "R-EU_R0603"))
    )
    (comp (ref "R48")
      (value "100k")
      (footprint "eagle-import:R0603")
      (libsource (lib "eagle-import") (part "R-EU_R0603"))
    )
    (comp (ref "R49")
      (value "100k")
      (footprint "eagle-import:R0603")
      (libsource (lib "eagle-import") (part "R-EU_R0603"))
    )
    (comp (ref "R50")
      (value "1k")
      (footprint "eagle-import:R0603")
      (libsource (lib "eagle-import") (part "R-EU_R0603"))
    )
    (comp (ref "R51")
      (value "1k")
      (footprint "eagle-import:R0603")
      (libsource (lib "eagle-import") (part "R-EU_R0603"))
    )
    (comp (ref "R52")
      (value "4k7")
      (footprint "eagle-import:R0603")
      (libsource (lib "eagle-import") (part "R-EU_R0603"))
    )
    (comp (ref "R54")
      (value "39k")
      (footprint "eagle-import:R0603")
      (libsource (lib "eagle-import") (part "R-EU_R0603"))
    )
    (comp (ref "R55")
      (value "39k")
      (footprint "eagle-import:R0603")
      (libsource (lib "eagle-import") (part "R-EU_R0603"))
    )
    (comp (ref "T1")
      (value "BC817")
      (footprint "eagle-import:SOT23-BEC")
      (libsource (lib "eagle-import") (part "-NPN-SOT23-BECBC817-16"))
    )
    (comp (ref "T2")
      (value "BC817")
      (footprint "eagle-import:SOT23-BEC")
      (libsource (lib "eagle-import") (part "-NPN-SOT23-BECBC817-16"))
    )
    (comp (ref "T3")
      (value "BC817")
      (footprint "eagle-import:SOT23-BEC")
      (libsource (lib "eagle-import") (part "-NPN-SOT23-BECBC817-16"))
    )
    (comp (ref "U1")
      (value "LM1117-3.3")
      (footprint "eagle-import:SOT-223")
      (fields (field (name "MPN") "CJT1117-3.3"))
      (libsource (lib "eagle-import") (part "PMIC-CJT1117-3.3(SOT223)"))
    )
    (comp (ref "U2")
      (value "10k")
      (footprint "eagle-import:SOP65P640X120-14")
      (fields
        (field (name "CONRAD") "1083246 - 62")
        (field (name "MOUSER") "579-MCP4641-103E/ST")
        (field (name "STOCK") "6")
      )
      (libsource (lib "eagle-import") (part "MCP46X1"))
    )
    (comp (ref "U3")
      (value "10k")
      (footprint "eagle-import:SOP65P640X120-14")
      (fields
        (field (name "CONRAD") "1083246 - 62")
        (field (name "MOUSER") "579-MCP4641-103E/ST")
        (field (name "STOCK") "6")
      )
      (libsource (lib "eagle-import") (part "MCP46X1"))
    )
    (comp (ref "U4")
      (value "10k")
      (footprint "eagle-import:SOP65P640X120-14")
      (fields
        (field (name "CONRAD") "1083246 - 62")
        (field (name "MOUSER") "579-MCP4641-103E/ST")
        (field (name "STOCK") "6")
      )
      (libsource (lib "eagle-import") (part "MCP46X1"))
    )
    (comp (ref "U5")
      (value "10k")
      (footprint "eagle-import:SOP65P640X120-14")
      (fields
        (field (name "CONRAD") "1083246 - 62")
        (field (name "MOUSER") "579-MCP4641-103E/ST")
        (field (name "STOCK") "6")
      )
      (libsource (lib "eagle-import") (part "MCP46X1"))
    )
    (comp (ref "U6")
      (value "TDA7498L")
      (footprint "eagle-import:SOP50P1010X245-36")
      (libsource (lib "eagle-import") (part "TDA7498L"))
    )
    (comp (ref "U7")
      (value "10k")
      (footprint "eagle-import:SOP65P640X120-14")
      (fields
        (field (name "CONRAD") "1083246 - 62")
        (field (name "MOUSER") "579-MCP4641-103E/ST")
        (field (name "STOCK") "6")
      )
      (libsource (lib "eagle-import") (part "MCP46X1"))
    )
    (comp (ref "U8")
      (value "10k")
      (footprint "eagle-import:SOP65P640X120-14")
      (fields
        (field (name "CONRAD") "1083246 - 62")
        (field (name "MOUSER") "579-MCP4641-103E/ST")
        (field (name "STOCK") "6")
      )
      (libsource (lib "eagle-import") (part "MCP46X1"))
    )
    (comp (ref "U9")
      (value "MCP9701SMD")
      (footprint "eagle-import:SOT23-3")
      (libsource (lib "eagle-import") (part "MCP9700SMD"))
    )
    (comp (ref "VR1")
      (value "100k")
      (footprint "eagle-import:TRIMPOT-SMD-TC33X")
      (libsource (lib "eagle-import") (part "TRIMPOT-SMD-3MM-OPEN-1/10W-25%"))
    )
    (comp (ref "X1")
      (value "RCA-4-CHANNEL")
      (footprint "eagle-import:BKL-072385")
      (fields
        (field (name "CONRAD") "1578879 - 62")
        (field (name "MOUSER") "806-KLP42X-61-WWRR")
        (field (name "STOCK") "1")
      )
      (libsource (lib "eagle-import") (part "RCA-4-CHANNEL"))
    )
    (comp (ref "X2")
      (value "JST-XH2")
      (footprint "eagle-import:JST-2-PTH-VERT")
      (libsource (lib "eagle-import") (part "JST-XH2"))
    )
    (comp (ref "X3")
      (value "ICSP")
      (footprint "eagle-import:057-006-1")
      (fields
        (field (name "CONRAD") "1560967 - 62")
        (field (name "MOUSER") "200-TSW10307TD")
        (field (name "STOCK") "1")
      )
      (libsource (lib "eagle-import") (part "CONN-IDC-6"))
    )
    (comp (ref "X4")
      (value "JST-XH2")
      (footprint "eagle-import:JST-2-PTH-VERT")
      (libsource (lib "eagle-import") (part "JST-XH2"))
    )
  )
  (nets
    (net (code "1") (name "+3V3") (class "Default")
      (node (ref "C10") (pin "1") (pinfunction "1_1") (pintype "passive"))
      (node (ref "C29") (pin "1") (pinfunction "1_1") (pintype "passive"))
      (node (ref "C43") (pin "1") (pinfunction "1_1") (pintype "passive"))
      (node (ref "C64") (pin "1") (pinfunction "1_1") (pintype "passive"))
      (node (ref "C65") (pin "1") (pinfunction "1_1") (pintype "passive"))
      (node (ref "C9") (pin "+") (pinfunction "+_+") (pintype "passive"))
      (node (ref "IC6") (pin "18") (pinfunction "AVCC_18") (pintype "power_in"))
      (node (ref "IC6") (pin "4") (pinfunction "VCC_4") (pintype "power_in"))
      (node (ref "IC6") (pin "6") (pinfunction "VCC_6") (pintype "power_in"))
      (node (ref "IC8") (pin "8") (pinfunction "V+_8") (pintype "power_in"))
      (node (ref "IC9") (pin "8") (pinfunction "V+_8") (pintype "power_in"))
      (node (ref "JP4") (pin "2") (pinfunction "2_2") (pintype "passive"))
      (node (ref "JP9") (pin "2") (pinfunction "2_2") (pintype "passive"))
      (node (ref "R13") (pin "2") (pinfunction "2_2") (pintype "passive"))
      (node (ref "R2") (pin "2") (pinfunction "2_2") (pintype "passive"))
      (node (ref "R52") (pin "2") (pinfunction "2_2") (pintype "passive"))
      (node (ref "U1") (pin "2") (pinfunction "OUT_2") (pintype "bidirectional"))
      (node (ref "U1") (pin "TER") (pinfunction "OUT_TER") (pintype "bidirectional"))
      (node (ref "U2") (pin "1") (pinfunction "A0/HVP_1") (pintype "bidirectional"))
      (node (ref "U2") (pin "11") (pinfunction "~{WP}_11") (pintype "bidirectional"))
      (node (ref "U2") (pin "12") (pinfunction "A2_12") (pintype "bidirectional"))
      (node (ref "U2") (pin "14") (pinfunction "VDD_14") (pintype "bidirectional"))
      (node (ref "U3") (pin "11") (pinfunction "~{WP}_11") (pintype "bidirectional"))
      (node (ref "U3") (pin "12") (pinfunction "A2_12") (pintype "bidirectional"))
      (node (ref "U3") (pin "14") (pinfunction "VDD_14") (pintype "bidirectional"))
      (node (ref "U4") (pin "1") (pinfunction "A0/HVP_1") (pintype "bidirectional"))
      (node (ref "U4") (pin "11") (pinfunction "~{WP}_11") (pintype "bidirectional"))
      (node (ref "U4") (pin "13") (pinfunction "A1_13") (pintype "bidirectional"))
      (node (ref "U4") (pin "14") (pinfunction "VDD_14") (pintype "bidirectional"))
      (node (ref "U5") (pin "11") (pinfunction "~{WP}_11") (pintype "bidirectional"))
      (node (ref "U5") (pin "13") (pinfunction "A1_13") (pintype "bidirectional"))
      (node (ref "U5") (pin "14") (pinfunction "VDD_14") (pintype "bidirectional"))
      (node (ref "U7") (pin "1") (pinfunction "A0/HVP_1") (pintype "bidirectional"))
      (node (ref "U7") (pin "11") (pinfunction "~{WP}_11") (pintype "bidirectional"))
      (node (ref "U7") (pin "14") (pinfunction "VDD_14") (pintype "bidirectional"))
      (node (ref "U8") (pin "11") (pinfunction "~{WP}_11") (pintype "bidirectional"))
      (node (ref "U8") (pin "14") (pinfunction "VDD_14") (pintype "bidirectional"))
      (node (ref "U9") (pin "1") (pinfunction "VCC_1") (pintype "bidirectional"))
      (node (ref "VR1") (pin "3") (pinfunction "CCW_3") (pintype "passive"))
    )
    (net (code "2") (name "+5V") (class "Default")
      (node (ref "C6") (pin "+") (pinfunction "+_+") (pintype "passive"))
      (node (ref "C63") (pin "2") (pinfunction "2_2") (pintype "passive"))
      (node (ref "C7") (pin "1") (pinfunction "1_1") (pintype "passive"))
      (node (ref "IC2") (pin "OUT") (pinfunction "OUT_OUT") (pintype "passive"))
      (node (ref "J8") (pin "2") (pinfunction "2_2") (pintype "passive"))
      (node (ref "J9") (pin "V+") (pinfunction "VBUS_V+") (pintype "power_in"))
    )
    (net (code "3") (name "+12V") (class "Default")
      (node (ref "C18") (pin "1") (pinfunction "1_1") (pintype "passive"))
      (node (ref "C21") (pin "1") (pinfunction "1_1") (pintype "passive"))
      (node (ref "C3") (pin "1") (pinfunction "1_1") (pintype "passive"))
      (node (ref "C4") (pin "+") (pinfunction "+_+") (pintype "passive"))
      (node (ref "C5") (pin "1") (pinfunction "1_1") (pintype "passive"))
      (node (ref "D1") (pin "A") (pinfunction "A_A") (pintype "passive"))
      (node (ref "D11") (pin "A") (pinfunction "A_A") (pintype "passive"))
      (node (ref "D3") (pin "C") (pinfunction "C_C") (pintype "passive"))
      (node (ref "D4") (pin "C") (pinfunction "C_C") (pintype "passive"))
      (node (ref "D8") (pin "C") (pinfunction "C_C") (pintype "passive"))
      (node (ref "IC1") (pin "OUT") (pinfunction "OUT_OUT") (pintype "passive"))
      (node (ref "IC2") (pin "IN") (pinfunction "IN_IN") (pintype "input"))
      (node (ref "IC4") (pin "8") (pinfunction "V+_8") (pintype "power_in"))
      (node (ref "IC5") (pin "8") (pinfunction "V+_8") (pintype "power_in"))
      (node (ref "JP7") (pin "2") (pinfunction "2_2") (pintype "passive"))
      (node (ref "K1") (pin "1") (pinfunction "1_1") (pintype "passive"))
      (node (ref "K2") (pin "1") (pinfunction "1_1") (pintype "passive"))
      (node (ref "R3") (pin "1") (pinfunction "1_1") (pintype "passive"))
      (node (ref "T3") (pin "C") (pinfunction "C_C") (pintype "passive"))
    )
    (net (code "4") (name "+12VAC") (class "Default")
      (node (ref "B1") (pin "AC1") (pinfunction "AC1_AC1") (pintype "passive"))
      (node (ref "D2") (pin "A") (pinfunction "A_A") (pintype "passive"))
      (node (ref "J1") (pin "P$1") (pinfunction "P$1_P$1") (pintype "bidirectional"))
      (node (ref "J1") (pin "P$2") (pinfunction "P$1_P$2") (pintype "bidirectional"))
    )
    (net (code "5") (name "+18V") (class "Default")
      (node (ref "C11") (pin "+") (pinfunction "+_+") (pintype "passive"))
      (node (ref "C12") (pin "+") (pinfunction "+_+") (pintype "passive"))
      (node (ref "C53") (pin "1") (pinfunction "1_1") (pintype "passive"))
      (node (ref "C54") (pin "1") (pinfunction "1_1") (pintype "passive"))
      (node (ref "C55") (pin "1") (pinfunction "1_1") (pintype "passive"))
      (node (ref "C56") (pin "1") (pinfunction "1_1") (pintype "passive"))
      (node (ref "K1") (pin "P1") (pinfunction "P_P1") (pintype "passive"))
      (node (ref "U6") (pin "12") (pinfunction "PVCCA_12") (pintype "bidirectional"))
      (node (ref "U6") (pin "13") (pinfunction "PVCCA_13") (pintype "bidirectional"))
      (node (ref "U6") (pin "6") (pinfunction "PVCCB_6") (pintype "bidirectional"))
      (node (ref "U6") (pin "7") (pinfunction "PVCCB_7") (pintype "bidirectional"))
    )
    (net (code "6") (name "-12V") (class "Default")
      (node (ref "C15") (pin "2") (pinfunction "2_2") (pintype "passive"))
      (node (ref "C16") (pin "-") (pinfunction "-_-") (pintype "passive"))
      (node (ref "C24") (pin "1") (pinfunction "1_1") (pintype "passive"))
      (node (ref "C34") (pin "1") (pinfunction "1_1") (pintype "passive"))
      (node (ref "D5") (pin "A") (pinfunction "A_A") (pintype "passive"))
      (node (ref "D7") (pin "C") (pinfunction "C_C") (pintype "passive"))
      (node (ref "IC3") (pin "OUT") (pinfunction "OUT_OUT") (pintype "passive"))
      (node (ref "IC4") (pin "4") (pinfunction "V-_4") (pintype "power_in"))
      (node (ref "IC5") (pin "4") (pinfunction "V-_4") (pintype "power_in"))
      (node (ref "JP8") (pin "2") (pinfunction "2_2") (pintype "passive"))
      (node (ref "R3") (pin "2") (pinfunction "2_2") (pintype "passive"))
    )
    (net (code "7") (name "-12VAC") (class "Default")
      (node (ref "B1") (pin "AC2") (pinfunction "AC2_AC2") (pintype "passive"))
      (node (ref "D6") (pin "C") (pinfunction "C_C") (pintype "passive"))
      (node (ref "J3") (pin "P$1") (pinfunction "P$1_P$1") (pintype "bidirectional"))
      (node (ref "J3") (pin "P$2") (pinfunction "P$1_P$2") (pintype "bidirectional"))
    )
    (net (code "8") (name "-18V") (class "Default")
      (node (ref "C11") (pin "-") (pinfunction "-_-") (pintype "passive"))
      (node (ref "C12") (pin "-") (pinfunction "-_-") (pintype "passive"))
      (node (ref "C53") (pin "2") (pinfunction "2_2") (pintype "passive"))
      (node (ref "C54") (pin "2") (pinfunction "2_2") (pintype "passive"))
      (node (ref "C55") (pin "2") (pinfunction "2_2") (pintype "passive"))
      (node (ref "C56") (pin "2") (pinfunction "2_2") (pintype "passive"))
      (node (ref "K1") (pin "P2") (pinfunction "P_P2") (pintype "passive"))
      (node (ref "U6") (pin "14") (pinfunction "PGNDA_14") (pintype "bidirectional"))
      (node (ref "U6") (pin "15") (pinfunction "PGNDA_15") (pintype "bidirectional"))
      (node (ref "U6") (pin "4") (pinfunction "PGNDB_4") (pintype "bidirectional"))
      (node (ref "U6") (pin "5") (pinfunction "PGNDB_5") (pintype "bidirectional"))
    )
    (net (code "9") (name "AGND") (class "Default")
      (node (ref "C18") (pin "2") (pinfunction "2_2") (pintype "passive"))
      (node (ref "C21") (pin "2") (pinfunction "2_2") (pintype "passive"))
      (node (ref "C24") (pin "2") (pinfunction "2_2") (pintype "passive"))
      (node (ref "C26") (pin "2") (pinfunction "2_2") (pintype "passive"))
      (node (ref "C27") (pin "1") (pinfunction "1_1") (pintype "passive"))
      (node (ref "C30") (pin "2") (pinfunction "2_2") (pintype "passive"))
      (node (ref "C31") (pin "1") (pinfunction "1_1") (pintype "passive"))
      (node (ref "C32") (pin "1") (pinfunction "1_1") (pintype "passive"))
      (node (ref "C33") (pin "1") (pinfunction "1_1") (pintype "passive"))
      (node (ref "C34") (pin "2") (pinfunction "2_2") (pintype "passive"))
      (node (ref "C36") (pin "1") (pinfunction "1_1") (pintype "passive"))
      (node (ref "C39") (pin "1") (pinfunction "1_1") (pintype "passive"))
      (node (ref "C40") (pin "1") (pinfunction "1_1") (pintype "passive"))
      (node (ref "C41") (pin "1") (pinfunction "1_1") (pintype "passive"))
      (node (ref "C42") (pin "2") (pinfunction "2_2") (pintype "passive"))
      (node (ref "C45") (pin "1") (pinfunction "1_1") (pintype "passive"))
      (node (ref "C46") (pin "2") (pinfunction "2_2") (pintype "passive"))
      (node (ref "C50") (pin "1") (pinfunction "1_1") (pintype "passive"))
      (node (ref "C60") (pin "-") (pinfunction "-_-") (pintype "passive"))
      (node (ref "C61") (pin "-") (pinfunction "-_-") (pintype "passive"))
      (node (ref "IC5") (pin "3") (pinfunction "+IN_3") (pintype "input"))
      (node (ref "IC5") (pin "5") (pinfunction "+IN_5") (pintype "input"))
      (node (ref "JP1") (pin "2") (pinfunction "AGND_2") (pintype "bidirectional"))
      (node (ref "JP5") (pin "3") (pinfunction "3_3") (pintype "passive"))
      (node (ref "JP5") (pin "4") (pinfunction "4_4") (pintype "passive"))
      (node (ref "JP6") (pin "3") (pinfunction "3_3") (pintype "passive"))
      (node (ref "JP6") (pin "4") (pinfunction "4_4") (pintype "passive"))
      (node (ref "R17") (pin "1") (pinfunction "1_1") (pintype "passive"))
      (node (ref "R18") (pin "2") (pinfunction "2_2") (pintype "passive"))
      (node (ref "R39") (pin "1") (pinfunction "1_1") (pintype "passive"))
      (node (ref "R40") (pin "2") (pinfunction "2_2") (pintype "passive"))
      (node (ref "U2") (pin "7") (pinfunction "A_7") (pintype "passive"))
      (node (ref "U2") (pin "8") (pinfunction "A_8") (pintype "passive"))
      (node (ref "U7") (pin "7") (pinfunction "A_7") (pintype "passive"))
      (node (ref "U7") (pin "8") (pinfunction "A_8") (pintype "passive"))
      (node (ref "U8") (pin "7") (pinfunction "A_7") (pintype "passive"))
      (node (ref "U8") (pin "8") (pinfunction "A_8") (pintype "passive"))
      (node (ref "X1") (pin "1") (pinfunction "S_1") (pintype "passive"))
      (node (ref "X1") (pin "4") (pinfunction "S_4") (pintype "passive"))
    )
    (net (code "10") (name "AMP_DIAG") (class "Default")
      (node (ref "IC6") (pin "23") (pinfunction "PC0(ADC0)_23") (pintype "bidirectional"))
      (node (ref "U6") (pin "28") (pinfunction "DIAG_28") (pintype "bidirectional"))
    )
    (net (code "11") (name "AMP_MUTE") (class "Default")
      (node (ref "IC6") (pin "2") (pinfunction "PD4(XCK/T0)_2") (pintype "bidirectional"))
      (node (ref "R54") (pin "2") (pinfunction "2_2") (pintype "passive"))
    )
    (net (code "12") (name "AMP_PWR") (class "Default")
      (node (ref "IC6") (pin "10") (pinfunction "PD6(AIN0)_10") (pintype "bidirectional"))
      (node (ref "T1") (pin "B") (pinfunction "B_B") (pintype "passive"))
    )
    (net (code "13") (name "AMP_STBY") (class "Default")
      (node (ref "IC6") (pin "9") (pinfunction "PD5(T1)_9") (pintype "bidirectional"))
      (node (ref "R55") (pin "2") (pinfunction "2_2") (pintype "passive"))
    )
    (net (code "14") (name "AUDIO_DETECT") (class "Default")
      (node (ref "IC6") (pin "32") (pinfunction "PD2(INT0)_32") (pintype "bidirectional"))
      (node (ref "R45") (pin "1") (pinfunction "1_1") (pintype "passive"))
    )
    (net (code "15") (name "DGND") (class "Default")
      (node (ref "C10") (pin "2") (pinfunction "2_2") (pintype "passive"))
      (node (ref "C23") (pin "1") (pinfunction "1_1") (pintype "passive"))
      (node (ref "C28") (pin "2") (pinfunction "2_2") (pintype "passive"))
      (node (ref "C29") (pin "2") (pinfunction "2_2") (pintype "passive"))
      (node (ref "C43") (pin "2") (pinfunction "2_2") (pintype "passive"))
      (node (ref "C5") (pin "2") (pinfunction "2_2") (pintype "passive"))
      (node (ref "C58") (pin "2") (pinfunction "2_2") (pintype "passive"))
      (node (ref "C6") (pin "-") (pinfunction "-_-") (pintype "passive"))
      (node (ref "C62") (pin "1") (pinfunction "1_1") (pintype "passive"))
      (node (ref "C63") (pin "1") (pinfunction "1_1") (pintype "passive"))
      (node (ref "C64") (pin "2") (pinfunction "2_2") (pintype "passive"))
      (node (ref "C65") (pin "2") (pinfunction "2_2") (pintype "passive"))
      (node (ref "C67") (pin "1") (pinfunction "1_1") (pintype "passive"))
      (node (ref "C7") (pin "2") (pinfunction "2_2") (pintype "passive"))
      (node (ref "C8") (pin "2") (pinfunction "2_2") (pintype "passive"))
      (node (ref "C9") (pin "-") (pinfunction "-_-") (pintype "passive"))
      (node (ref "D10") (pin "A") (pinfunction "A_A") (pintype "passive"))
      (node (ref "IC2") (pin "GND") (pinfunction "GND_GND") (pintype "input"))
      (node (ref "IC6") (pin "21") (pinfunction "GND_21") (pintype "power_in"))
      (node (ref "IC6") (pin "3") (pinfunction "GND_3") (pintype "power_in"))
      (node (ref "IC6") (pin "5") (pinfunction "GND_5") (pintype "power_in"))
      (node (ref "IC8") (pin "4") (pinfunction "V-_4") (pintype "power_in"))
      (node (ref "IC9") (pin "4") (pinfunction "V-_4") (pintype "power_in"))
      (node (ref "J10") (pin "2") (pinfunction "2_2") (pintype "passive"))
      (node (ref "J7") (pin "1") (pinfunction "1_1") (pintype "passive"))
      (node (ref "J8") (pin "1") (pinfunction "1_1") (pintype "passive"))
      (node (ref "J9") (pin "V-") (pinfunction "GND_V-") (pintype "power_in"))
      (node (ref "JP1") (pin "1") (pinfunction "DGND_1") (pintype "bidirectional"))
      (node (ref "JP4") (pin "1") (pinfunction "1_1") (pintype "passive"))
      (node (ref "JP9") (pin "1") (pinfunction "1_1") (pintype "passive"))
      (node (ref "LED1") (pin "C") (pinfunction "C_C") (pintype "passive"))
      (node (ref "R41") (pin "1") (pinfunction "1_1") (pintype "passive"))
      (node (ref "R48") (pin "1") (pinfunction "1_1") (pintype "passive"))
      (node (ref "R50") (pin "1") (pinfunction "1_1") (pintype "passive"))
      (node (ref "R51") (pin "1") (pinfunction "1_1") (pintype "passive"))
      (node (ref "T2") (pin "E") (pinfunction "E_E") (pintype "passive"))
      (node (ref "U1") (pin "1") (pinfunction "GND_1") (pintype "bidirectional"))
      (node (ref "U2") (pin "13") (pinfunction "A1_13") (pintype "bidirectional"))
      (node (ref "U2") (pin "4") (pinfunction "VSS_4") (pintype "bidirectional"))
      (node (ref "U3") (pin "1") (pinfunction "A0/HVP_1") (pintype "bidirectional"))
      (node (ref "U3") (pin "13") (pinfunction "A1_13") (pintype "bidirectional"))
      (node (ref "U3") (pin "4") (pinfunction "VSS_4") (pintype "bidirectional"))
      (node (ref "U4") (pin "12") (pinfunction "A2_12") (pintype "bidirectional"))
      (node (ref "U4") (pin "4") (pinfunction "VSS_4") (pintype "bidirectional"))
      (node (ref "U5") (pin "1") (pinfunction "A0/HVP_1") (pintype "bidirectional"))
      (node (ref "U5") (pin "12") (pinfunction "A2_12") (pintype "bidirectional"))
      (node (ref "U5") (pin "4") (pinfunction "VSS_4") (pintype "bidirectional"))
      (node (ref "U6") (pin "27") (pinfunction "SGND_27") (pintype "bidirectional"))
      (node (ref "U7") (pin "12") (pinfunction "A2_12") (pintype "bidirectional"))
      (node (ref "U7") (pin "13") (pinfunction "A1_13") (pintype "bidirectional"))
      (node (ref "U7") (pin "4") (pinfunction "VSS_4") (pintype "bidirectional"))
      (node (ref "U8") (pin "1") (pinfunction "A0/HVP_1") (pintype "bidirectional"))
      (node (ref "U8") (pin "12") (pinfunction "A2_12") (pintype "bidirectional"))
      (node (ref "U8") (pin "13") (pinfunction "A1_13") (pintype "bidirectional"))
      (node (ref "U8") (pin "4") (pinfunction "VSS_4") (pintype "bidirectional"))
      (node (ref "U9") (pin "3") (pinfunction "GND_3") (pintype "bidirectional"))
      (node (ref "VR1") (pin "1") (pinfunction "CW_1") (pintype "passive"))
      (node (ref "X2") (pin "1") (pinfunction "1_1") (pintype "passive"))
      (node (ref "X3") (pin "6") (pinfunction "S_6") (pintype "passive"))
      (node (ref "X4") (pin "1") (pinfunction "1_1") (pintype "passive"))
    )
    (net (code "16") (name "ENC_BTN") (class "Default")
      (node (ref "IC6") (pin "25") (pinfunction "PC2(ADC2)_25") (pintype "bidirectional"))
      (node (ref "J7") (pin "2") (pinfunction "2_2") (pintype "passive"))
    )
    (net (code "17") (name "EQ_L") (class "Default")
      (node (ref "IC4") (pin "5") (pinfunction "+IN_5") (pintype "input"))
      (node (ref "JP5") (pin "6") (pinfunction "6_6") (pintype "passive"))
    )
    (net (code "18") (name "EQ_R") (class "Default")
      (node (ref "IC4") (pin "3") (pinfunction "+IN_3") (pintype "input"))
      (node (ref "JP5") (pin "2") (pinfunction "2_2") (pintype "passive"))
    )
    (net (code "19") (name "FAN_CTL") (class "Default")
      (node (ref "IC6") (pin "15") (pinfunction "PB3(MOSI/OC2)_15") (pintype "bidirectional"))
      (node (ref "T3") (pin "B") (pinfunction "B_B") (pintype "passive"))
      (node (ref "X3") (pin "4") (pinfunction "S_4") (pintype "passive"))
    )
    (net (code "20") (name "GAIN0") (class "Default")
      (node (ref "IC6") (pin "16") (pinfunction "PB4(MISO)_16") (pintype "bidirectional"))
      (node (ref "U6") (pin "30") (pinfunction "GAIN0_30") (pintype "bidirectional"))
      (node (ref "X3") (pin "1") (pinfunction "S_1") (pintype "passive"))
    )
    (net (code "21") (name "GAIN1") (class "Default")
      (node (ref "IC6") (pin "17") (pinfunction "PB5(SCK)_17") (pintype "bidirectional"))
      (node (ref "U6") (pin "31") (pinfunction "GAIN1_31") (pintype "bidirectional"))
      (node (ref "X3") (pin "3") (pinfunction "S_3") (pintype "passive"))
    )
    (net (code "22") (name "GND") (class "Default")
      (node (ref "C1") (pin "-") (pinfunction "-_-") (pintype "passive"))
      (node (ref "C13") (pin "+") (pinfunction "+_+") (pintype "passive"))
      (node (ref "C14") (pin "1") (pinfunction "1_1") (pintype "passive"))
      (node (ref "C15") (pin "1") (pinfunction "1_1") (pintype "passive"))
      (node (ref "C16") (pin "+") (pinfunction "+_+") (pintype "passive"))
      (node (ref "C2") (pin "2") (pinfunction "2_2") (pintype "passive"))
      (node (ref "C3") (pin "2") (pinfunction "2_2") (pintype "passive"))
      (node (ref "C4") (pin "-") (pinfunction "-_-") (pintype "passive"))
      (node (ref "D3") (pin "A") (pinfunction "A_A") (pintype "passive"))
      (node (ref "D5") (pin "C") (pinfunction "C_C") (pintype "passive"))
      (node (ref "IC1") (pin "GND") (pinfunction "GND_GND") (pintype "input"))
      (node (ref "IC3") (pin "GND") (pinfunction "GND_GND") (pintype "input"))
      (node (ref "J2") (pin "P$1") (pinfunction "P$1_P$1") (pintype "bidirectional"))
      (node (ref "J2") (pin "P$2") (pinfunction "P$1_P$2") (pintype "bidirectional"))
      (node (ref "JP1") (pin "3") (pinfunction "GND_3") (pintype "bidirectional"))
      (node (ref "JP10") (pin "1") (pinfunction "1_1") (pintype "passive"))
      (node (ref "JP7") (pin "1") (pinfunction "1_1") (pintype "passive"))
      (node (ref "JP8") (pin "1") (pinfunction "1_1") (pintype "passive"))
      (node (ref "KK1") (pin "K1") (pinfunction "K_K1") (pintype "passive"))
      (node (ref "KK1") (pin "K2") (pinfunction "K_K2") (pintype "passive"))
      (node (ref "KK4") (pin "K1") (pinfunction "K_K1") (pintype "passive"))
      (node (ref "KK4") (pin "K2") (pinfunction "K_K2") (pintype "passive"))
      (node (ref "T1") (pin "E") (pinfunction "E_E") (pintype "passive"))
    )
    (net (code "23") (name "L_OUT+") (class "Default")
      (node (ref "C42") (pin "1") (pinfunction "1_1") (pintype "passive"))
      (node (ref "C44") (pin "1") (pinfunction "1_1") (pintype "passive"))
      (node (ref "K2") (pin "S1") (pinfunction "S_S1") (pintype "passive"))
      (node (ref "L3") (pin "2") (pinfunction "2_2") (pintype "passive"))
      (node (ref "R24") (pin "2") (pinfunction "2_2") (pintype "passive"))
    )
    (net (code "24") (name "L_OUT-") (class "Default")
      (node (ref "C44") (pin "2") (pinfunction "2_2") (pintype "passive"))
      (node (ref "C45") (pin "2") (pinfunction "2_2") (pintype "passive"))
      (node (ref "J6") (pin "1") (pinfunction "P$1_1") (pintype "bidirectional"))
      (node (ref "L4") (pin "2") (pinfunction "2_2") (pintype "passive"))
      (node (ref "R34") (pin "1") (pinfunction "1_1") (pintype "passive"))
    )
    (net (code "25") (name "MIX_L") (class "Default")
      (node (ref "IC8") (pin "5") (pinfunction "+IN_5") (pintype "input"))
      (node (ref "JP5") (pin "5") (pinfunction "5_5") (pintype "passive"))
      (node (ref "R19") (pin "2") (pinfunction "2_2") (pintype "passive"))
      (node (ref "R35") (pin "2") (pinfunction "2_2") (pintype "passive"))
    )
    (net (code "26") (name "MIX_R") (class "Default")
      (node (ref "IC8") (pin "3") (pinfunction "+IN_3") (pintype "input"))
      (node (ref "JP5") (pin "1") (pinfunction "1_1") (pintype "passive"))
      (node (ref "R11") (pin "2") (pinfunction "2_2") (pintype "passive"))
      (node (ref "R28") (pin "2") (pinfunction "2_2") (pintype "passive"))
    )
    (net (code "27") (name "Net-(C1-Pad+)") (class "Default")
      (node (ref "C1") (pin "+") (pinfunction "+_+") (pintype "passive"))
      (node (ref "C2") (pin "1") (pinfunction "1_1") (pintype "passive"))
      (node (ref "D1") (pin "C") (pinfunction "C_C") (pintype "passive"))
      (node (ref "D2") (pin "C") (pinfunction "C_C") (pintype "passive"))
      (node (ref "IC1") (pin "IN") (pinfunction "IN_IN") (pintype "input"))
    )
    (net (code "28") (name "Net-(C13-Pad-)") (class "Default")
      (node (ref "C13") (pin "-") (pinfunction "-_-") (pintype "passive"))
      (node (ref "C14") (pin "2") (pinfunction "2_2") (pintype "passive"))
      (node (ref "D6") (pin "A") (pinfunction "A_A") (pintype "passive"))
      (node (ref "D7") (pin "A") (pinfunction "A_A") (pintype "passive"))
      (node (ref "IC3") (pin "IN") (pinfunction "IN_IN") (pintype "input"))
    )
    (net (code "29") (name "Net-(C19-Pad1)") (class "Default")
      (node (ref "C19") (pin "1") (pinfunction "1_1") (pintype "passive"))
      (node (ref "R12") (pin "2") (pinfunction "2_2") (pintype "passive"))
      (node (ref "R8") (pin "1") (pinfunction "1_1") (pintype "passive"))
    )
    (net (code "30") (name "Net-(C20-Pad2)") (class "Default")
      (node (ref "C20") (pin "2") (pinfunction "2_2") (pintype "passive"))
      (node (ref "JP2") (pin "2") (pinfunction "2_2") (pintype "passive"))
      (node (ref "R14") (pin "2") (pinfunction "2_2") (pintype "passive"))
      (node (ref "R17") (pin "2") (pinfunction "2_2") (pintype "passive"))
      (node (ref "R4") (pin "2") (pinfunction "2_2") (pintype "passive"))
      (node (ref "R6") (pin "2") (pinfunction "2_2") (pintype "passive"))
      (node (ref "R9") (pin "2") (pinfunction "2_2") (pintype "passive"))
    )
    (net (code "31") (name "Net-(C22-Pad1)") (class "Default")
      (node (ref "C22") (pin "1") (pinfunction "1_1") (pintype "passive"))
      (node (ref "JP6") (pin "1") (pinfunction "1_1") (pintype "passive"))
    )
    (net (code "32") (name "Net-(C26-Pad1)") (class "Default")
      (node (ref "C26") (pin "1") (pinfunction "1_1") (pintype "passive"))
      (node (ref "R16") (pin "1") (pinfunction "1_1") (pintype "passive"))
    )
    (net (code "33") (name "Net-(C31-Pad2)") (class "Default")
      (node (ref "C31") (pin "2") (pinfunction "2_2") (pintype "passive"))
      (node (ref "R22") (pin "2") (pinfunction "2_2") (pintype "passive"))
    )
    (net (code "34") (name "Net-(C37-Pad1)") (class "Default")
      (node (ref "C37") (pin "1") (pinfunction "1_1") (pintype "passive"))
      (node (ref "JP6") (pin "5") (pinfunction "5_5") (pintype "passive"))
    )
    (net (code "35") (name "Net-(C38-Pad1)") (class "Default")
      (node (ref "C38") (pin "1") (pinfunction "1_1") (pintype "passive"))
      (node (ref "R20") (pin "1") (pinfunction "1_1") (pintype "passive"))
    )
    (net (code "36") (name "Net-(C38-Pad2)") (class "Default")
      (node (ref "C38") (pin "2") (pinfunction "2_2") (pintype "passive"))
      (node (ref "L2") (pin "1") (pinfunction "1_1") (pintype "passive"))
      (node (ref "U6") (pin "10") (pinfunction "OUTNA_10") (pintype "bidirectional"))
      (node (ref "U6") (pin "11") (pinfunction "OUTNA_11") (pintype "bidirectional"))
    )
    (net (code "37") (name "Net-(C46-Pad1)") (class "Default")
      (node (ref "C46") (pin "1") (pinfunction "1_1") (pintype "passive"))
      (node (ref "R24") (pin "1") (pinfunction "1_1") (pintype "passive"))
    )
    (net (code "38") (name "Net-(C47-Pad1)") (class "Default")
      (node (ref "C47") (pin "1") (pinfunction "1_1") (pintype "passive"))
      (node (ref "R23") (pin "1") (pinfunction "1_1") (pintype "passive"))
    )
    (net (code "39") (name "Net-(C47-Pad2)") (class "Default")
      (node (ref "C47") (pin "2") (pinfunction "2_2") (pintype "passive"))
      (node (ref "L4") (pin "1") (pinfunction "1_1") (pintype "passive"))
      (node (ref "U6") (pin "8") (pinfunction "OUTNB_8") (pintype "bidirectional"))
      (node (ref "U6") (pin "9") (pinfunction "OUTNB_9") (pintype "bidirectional"))
    )
    (net (code "40") (name "Net-(C50-Pad2)") (class "Default")
      (node (ref "C50") (pin "2") (pinfunction "2_2") (pintype "passive"))
      (node (ref "R34") (pin "2") (pinfunction "2_2") (pintype "passive"))
    )
    (net (code "41") (name "Net-(C51-Pad1)") (class "Default")
      (node (ref "C51") (pin "1") (pinfunction "1_1") (pintype "passive"))
      (node (ref "R31") (pin "1") (pinfunction "1_1") (pintype "passive"))
      (node (ref "R36") (pin "2") (pinfunction "2_2") (pintype "passive"))
    )
    (net (code "42") (name "Net-(C57-Pad2)") (class "Default")
      (node (ref "C57") (pin "2") (pinfunction "2_2") (pintype "passive"))
      (node (ref "JP3") (pin "2") (pinfunction "2_2") (pintype "passive"))
      (node (ref "R25") (pin "2") (pinfunction "2_2") (pintype "passive"))
      (node (ref "R29") (pin "2") (pinfunction "2_2") (pintype "passive"))
      (node (ref "R32") (pin "2") (pinfunction "2_2") (pintype "passive"))
      (node (ref "R37") (pin "2") (pinfunction "2_2") (pintype "passive"))
      (node (ref "R39") (pin "2") (pinfunction "2_2") (pintype "passive"))
    )
    (net (code "43") (name "Net-(C66-Pad1)") (class "Default")
      (node (ref "C66") (pin "1") (pinfunction "1_1") (pintype "passive"))
      (node (ref "R44") (pin "1") (pinfunction "1_1") (pintype "passive"))
      (node (ref "R47") (pin "2") (pinfunction "2_2") (pintype "passive"))
    )
    (net (code "44") (name "Net-(C67-Pad2)") (class "Default")
      (node (ref "C67") (pin "2") (pinfunction "2_2") (pintype "passive"))
      (node (ref "D9") (pin "C") (pinfunction "C_C") (pintype "passive"))
      (node (ref "R46") (pin "2") (pinfunction "2_2") (pintype "passive"))
      (node (ref "R50") (pin "2") (pinfunction "2_2") (pintype "passive"))
    )
    (net (code "45") (name "Net-(D4-PadA)") (class "Default")
      (node (ref "D4") (pin "A") (pinfunction "A_A") (pintype "passive"))
      (node (ref "K1") (pin "2") (pinfunction "2_2") (pintype "passive"))
      (node (ref "T1") (pin "C") (pinfunction "C_C") (pintype "passive"))
    )
    (net (code "46") (name "Net-(D8-PadA)") (class "Default")
      (node (ref "D8") (pin "A") (pinfunction "A_A") (pintype "passive"))
      (node (ref "K2") (pin "2") (pinfunction "2_2") (pintype "passive"))
      (node (ref "T2") (pin "C") (pinfunction "C_C") (pintype "passive"))
    )
    (net (code "47") (name "Net-(D10-PadC)") (class "Default")
      (node (ref "D10") (pin "C") (pinfunction "C_C") (pintype "passive"))
      (node (ref "J10") (pin "1") (pinfunction "1_1") (pintype "passive"))
      (node (ref "T3") (pin "E") (pinfunction "E_E") (pintype "passive"))
    )
    (net (code "48") (name "Net-(IC4A--IN)") (class "Default")
      (node (ref "IC4") (pin "2") (pinfunction "-IN_2") (pintype "input"))
      (node (ref "R18") (pin "1") (pinfunction "1_1") (pintype "passive"))
      (node (ref "R21") (pin "2") (pinfunction "2_2") (pintype "passive"))
    )
    (net (code "49") (name "Net-(IC4A-OUT)") (class "Default")
      (node (ref "C20") (pin "1") (pinfunction "1_1") (pintype "passive"))
      (node (ref "IC4") (pin "1") (pinfunction "OUT_1") (pintype "output"))
      (node (ref "JP2") (pin "1") (pinfunction "1_1") (pintype "passive"))
      (node (ref "R21") (pin "1") (pinfunction "1_1") (pintype "passive"))
    )
    (net (code "50") (name "Net-(IC4B--IN)") (class "Default")
      (node (ref "IC4") (pin "6") (pinfunction "-IN_6") (pintype "input"))
      (node (ref "R40") (pin "1") (pinfunction "1_1") (pintype "passive"))
      (node (ref "R42") (pin "2") (pinfunction "2_2") (pintype "passive"))
    )
    (net (code "51") (name "Net-(IC4B-OUT)") (class "Default")
      (node (ref "C57") (pin "1") (pinfunction "1_1") (pintype "passive"))
      (node (ref "IC4") (pin "7") (pinfunction "OUT_7") (pintype "output"))
      (node (ref "JP3") (pin "1") (pinfunction "1_1") (pintype "passive"))
      (node (ref "R42") (pin "1") (pinfunction "1_1") (pintype "passive"))
    )
    (net (code "52") (name "Net-(IC5A--IN)") (class "Default")
      (node (ref "C25") (pin "1") (pinfunction "1_1") (pintype "passive"))
      (node (ref "IC5") (pin "2") (pinfunction "-IN_2") (pintype "input"))
      (node (ref "R12") (pin "1") (pinfunction "1_1") (pintype "passive"))
    )
    (net (code "53") (name "Net-(IC5A-OUT)") (class "Default")
      (node (ref "IC5") (pin "1") (pinfunction "OUT_1") (pintype "output"))
      (node (ref "R10") (pin "1") (pinfunction "1_1") (pintype "passive"))
      (node (ref "R15") (pin "1") (pinfunction "1_1") (pintype "passive"))
      (node (ref "R5") (pin "1") (pinfunction "1_1") (pintype "passive"))
      (node (ref "R7") (pin "1") (pinfunction "1_1") (pintype "passive"))
      (node (ref "U2") (pin "5") (pinfunction "B_5") (pintype "passive"))
    )
    (net (code "54") (name "Net-(IC5B--IN)") (class "Default")
      (node (ref "C59") (pin "1") (pinfunction "1_1") (pintype "passive"))
      (node (ref "IC5") (pin "6") (pinfunction "-IN_6") (pintype "input"))
      (node (ref "R36") (pin "1") (pinfunction "1_1") (pintype "passive"))
    )
    (net (code "55") (name "Net-(IC5B-OUT)") (class "Default")
      (node (ref "IC5") (pin "7") (pinfunction "OUT_7") (pintype "output"))
      (node (ref "R26") (pin "1") (pinfunction "1_1") (pintype "passive"))
      (node (ref "R30") (pin "1") (pinfunction "1_1") (pintype "passive"))
      (node (ref "R33") (pin "1") (pinfunction "1_1") (pintype "passive"))
      (node (ref "R38") (pin "1") (pinfunction "1_1") (pintype "passive"))
      (node (ref "U2") (pin "10") (pinfunction "B_10") (pintype "passive"))
    )
    (net (code "56") (name "Net-(IC6-AREF)") (class "Default")
      (node (ref "C28") (pin "1") (pinfunction "1_1") (pintype "passive"))
      (node (ref "IC6") (pin "20") (pinfunction "AREF_20") (pintype "passive"))
    )
    (net (code "57") (name "Net-(IC6-PB0(ICP))") (class "Default")
      (node (ref "IC6") (pin "12") (pinfunction "PB0(ICP)_12") (pintype "bidirectional"))
      (node (ref "J7") (pin "4") (pinfunction "4_4") (pintype "passive"))
    )
    (net (code "58") (name "Net-(IC6-PB1(OC1A))") (class "Default")
      (node (ref "IC6") (pin "13") (pinfunction "PB1(OC1A)_13") (pintype "bidirectional"))
      (node (ref "J7") (pin "3") (pinfunction "3_3") (pintype "passive"))
    )
    (net (code "59") (name "Net-(IC6-PC6({slash}RESET))") (class "Default")
      (node (ref "C23") (pin "2") (pinfunction "2_2") (pintype "passive"))
      (node (ref "IC6") (pin "29") (pinfunction "PC6(/RESET)_29") (pintype "bidirectional"))
      (node (ref "R13") (pin "1") (pinfunction "1_1") (pintype "passive"))
      (node (ref "X3") (pin "5") (pinfunction "S_5") (pintype "passive"))
    )
    (net (code "60") (name "Net-(IC6-PD0(RXD))") (class "Default")
      (node (ref "IC6") (pin "30") (pinfunction "PD0(RXD)_30") (pintype "bidirectional"))
      (node (ref "JP4") (pin "4") (pinfunction "4_4") (pintype "passive"))
    )
    (net (code "61") (name "Net-(IC6-PD1(TXD))") (class "Default")
      (node (ref "IC6") (pin "31") (pinfunction "PD1(TXD)_31") (pintype "bidirectional"))
      (node (ref "JP4") (pin "3") (pinfunction "3_3") (pintype "passive"))
    )
    (net (code "62") (name "Net-(IC8A--IN)") (class "Default")
      (node (ref "IC8") (pin "1") (pinfunction "OUT_1") (pintype "output"))
      (node (ref "IC8") (pin "2") (pinfunction "-IN_2") (pintype "input"))
      (node (ref "R44") (pin "2") (pinfunction "2_2") (pintype "passive"))
    )
    (net (code "63") (name "Net-(IC8B--IN)") (class "Default")
      (node (ref "IC8") (pin "6") (pinfunction "-IN_6") (pintype "input"))
      (node (ref "IC8") (pin "7") (pinfunction "OUT_7") (pintype "output"))
      (node (ref "R47") (pin "1") (pinfunction "1_1") (pintype "passive"))
    )
    (net (code "64") (name "Net-(IC9A-+IN)") (class "Default")
      (node (ref "C66") (pin "2") (pinfunction "2_2") (pintype "passive"))
      (node (ref "IC9") (pin "3") (pinfunction "+IN_3") (pintype "input"))
      (node (ref "R48") (pin "2") (pinfunction "2_2") (pintype "passive"))
    )
    (net (code "65") (name "Net-(IC9A--IN)") (class "Default")
      (node (ref "IC9") (pin "2") (pinfunction "-IN_2") (pintype "input"))
      (node (ref "R49") (pin "2") (pinfunction "2_2") (pintype "passive"))
      (node (ref "R51") (pin "2") (pinfunction "2_2") (pintype "passive"))
    )
    (net (code "66") (name "Net-(IC9A-OUT)") (class "Default")
      (node (ref "D9") (pin "A") (pinfunction "A_A") (pintype "passive"))
      (node (ref "IC9") (pin "1") (pinfunction "OUT_1") (pintype "output"))
      (node (ref "R49") (pin "1") (pinfunction "1_1") (pintype "passive"))
    )
    (net (code "67") (name "Net-(IC9B-+IN)") (class "Default")
      (node (ref "IC9") (pin "5") (pinfunction "+IN_5") (pintype "input"))
      (node (ref "VR1") (pin "2") (pinfunction "WIPER_2") (pintype "passive"))
    )
    (net (code "68") (name "Net-(IC9B--IN)") (class "Default")
      (node (ref "IC9") (pin "6") (pinfunction "-IN_6") (pintype "input"))
      (node (ref "R46") (pin "1") (pinfunction "1_1") (pintype "passive"))
    )
    (net (code "69") (name "Net-(IC9B-OUT)") (class "Default")
      (node (ref "IC9") (pin "7") (pinfunction "OUT_7") (pintype "output"))
      (node (ref "R43") (pin "1") (pinfunction "1_1") (pintype "passive"))
      (node (ref "R45") (pin "2") (pinfunction "2_2") (pintype "passive"))
    )
    (net (code "70") (name "Net-(J5A-P$1)") (class "Default")
      (node (ref "J5") (pin "1") (pinfunction "P$1_1") (pintype "bidirectional"))
      (node (ref "K2") (pin "P2") (pinfunction "P_P2") (pintype "passive"))
    )
    (net (code "71") (name "Net-(J6B-P$1)") (class "Default")
      (node (ref "J6") (pin "2") (pinfunction "P$1_2") (pintype "bidirectional"))
      (node (ref "K2") (pin "P1") (pinfunction "P_P1") (pintype "passive"))
    )
    (net (code "72") (name "Net-(K1B-O)") (class "Default")
      (node (ref "K1") (pin "O1") (pinfunction "O_O1") (pintype "passive"))
      (node (ref "R1") (pin "1") (pinfunction "1_1") (pintype "passive"))
    )
    (net (code "73") (name "Net-(K1B-S)") (class "Default")
      (node (ref "B1") (pin "+") (pinfunction "+_+") (pintype "passive"))
      (node (ref "K1") (pin "S1") (pinfunction "S_S1") (pintype "passive"))
    )
    (net (code "74") (name "Net-(K1C-O)") (class "Default")
      (node (ref "K1") (pin "O2") (pinfunction "O_O2") (pintype "passive"))
      (node (ref "R1") (pin "2") (pinfunction "2_2") (pintype "passive"))
    )
    (net (code "75") (name "Net-(K1C-S)") (class "Default")
      (node (ref "B1") (pin "-") (pinfunction "-_-") (pintype "passive"))
      (node (ref "K1") (pin "S2") (pinfunction "S_S2") (pintype "passive"))
    )
    (net (code "76") (name "Net-(L1-Pad1)") (class "Default")
      (node (ref "L1") (pin "1") (pinfunction "1_1") (pintype "passive"))
      (node (ref "R20") (pin "2") (pinfunction "2_2") (pintype "passive"))
      (node (ref "U6") (pin "16") (pinfunction "OUTPA_16") (pintype "bidirectional"))
      (node (ref "U6") (pin "17") (pinfunction "OUTPA_17") (pintype "bidirectional"))
    )
    (net (code "77") (name "Net-(L3-Pad1)") (class "Default")
      (node (ref "L3") (pin "1") (pinfunction "1_1") (pintype "passive"))
      (node (ref "R23") (pin "2") (pinfunction "2_2") (pintype "passive"))
      (node (ref "U6") (pin "2") (pinfunction "OUTPB_2") (pintype "bidirectional"))
      (node (ref "U6") (pin "3") (pinfunction "OUTPB_3") (pintype "bidirectional"))
    )
    (net (code "78") (name "Net-(LED1-PadA)") (class "Default")
      (node (ref "LED1") (pin "A") (pinfunction "A_A") (pintype "passive"))
      (node (ref "R43") (pin "2") (pinfunction "2_2") (pintype "passive"))
    )
    (net (code "79") (name "Net-(U1-IN)") (class "Default")
      (node (ref "C8") (pin "1") (pinfunction "1_1") (pintype "passive"))
      (node (ref "D11") (pin "C") (pinfunction "C_C") (pintype "passive"))
      (node (ref "D12") (pin "C") (pinfunction "C_C") (pintype "passive"))
      (node (ref "U1") (pin "3") (pinfunction "IN_3") (pintype "bidirectional"))
    )
    (net (code "80") (name "Net-(U2B-W)") (class "Default")
      (node (ref "JP6") (pin "6") (pinfunction "6_6") (pintype "passive"))
      (node (ref "U2") (pin "9") (pinfunction "W_9") (pintype "passive"))
    )
    (net (code "81") (name "Net-(U2C-W)") (class "Default")
      (node (ref "JP6") (pin "2") (pinfunction "2_2") (pintype "passive"))
      (node (ref "U2") (pin "6") (pinfunction "W_6") (pintype "passive"))
    )
    (net (code "82") (name "Net-(U3B-A)") (class "Default")
      (node (ref "R4") (pin "1") (pinfunction "1_1") (pintype "passive"))
      (node (ref "U3") (pin "8") (pinfunction "A_8") (pintype "passive"))
    )
    (net (code "83") (name "Net-(U3B-B)") (class "Default")
      (node (ref "R5") (pin "2") (pinfunction "2_2") (pintype "passive"))
      (node (ref "U3") (pin "10") (pinfunction "B_10") (pintype "passive"))
    )
    (net (code "84") (name "Net-(U3B-W)") (class "Default")
      (node (ref "R8") (pin "2") (pinfunction "2_2") (pintype "passive"))
      (node (ref "U3") (pin "9") (pinfunction "W_9") (pintype "passive"))
    )
    (net (code "85") (name "Net-(U3C-A)") (class "Default")
      (node (ref "R25") (pin "1") (pinfunction "1_1") (pintype "passive"))
      (node (ref "U3") (pin "7") (pinfunction "A_7") (pintype "passive"))
    )
    (net (code "86") (name "Net-(U3C-B)") (class "Default")
      (node (ref "R26") (pin "2") (pinfunction "2_2") (pintype "passive"))
      (node (ref "U3") (pin "5") (pinfunction "B_5") (pintype "passive"))
    )
    (net (code "87") (name "Net-(U3C-W)") (class "Default")
      (node (ref "R31") (pin "2") (pinfunction "2_2") (pintype "passive"))
      (node (ref "U3") (pin "6") (pinfunction "W_6") (pintype "passive"))
    )
    (net (code "88") (name "Net-(U4B-A)") (class "Default")
      (node (ref "C17") (pin "1") (pinfunction "1_1") (pintype "passive"))
      (node (ref "R6") (pin "1") (pinfunction "1_1") (pintype "passive"))
      (node (ref "R9") (pin "1") (pinfunction "1_1") (pintype "passive"))
      (node (ref "U4") (pin "8") (pinfunction "A_8") (pintype "passive"))
    )
    (net (code "89") (name "Net-(U4B-B)") (class "Default")
      (node (ref "C17") (pin "2") (pinfunction "2_2") (pintype "passive"))
      (node (ref "R10") (pin "2") (pinfunction "2_2") (pintype "passive"))
      (node (ref "R7") (pin "2") (pinfunction "2_2") (pintype "passive"))
      (node (ref "U4") (pin "10") (pinfunction "B_10") (pintype "passive"))
    )
    (net (code "90") (name "Net-(U4B-W)") (class "Default")
      (node (ref "C19") (pin "2") (pinfunction "2_2") (pintype "passive"))
      (node (ref "U4") (pin "9") (pinfunction "W_9") (pintype "passive"))
    )
    (net (code "91") (name "Net-(U4C-A)") (class "Default")
      (node (ref "C48") (pin "1") (pinfunction "1_1") (pintype "passive"))
      (node (ref "R29") (pin "1") (pinfunction "1_1") (pintype "passive"))
      (node (ref "R32") (pin "1") (pinfunction "1_1") (pintype "passive"))
      (node (ref "U4") (pin "7") (pinfunction "A_7") (pintype "passive"))
    )
    (net (code "92") (name "Net-(U4C-B)") (class "Default")
      (node (ref "C48") (pin "2") (pinfunction "2_2") (pintype "passive"))
      (node (ref "R30") (pin "2") (pinfunction "2_2") (pintype "passive"))
      (node (ref "R33") (pin "2") (pinfunction "2_2") (pintype "passive"))
      (node (ref "U4") (pin "5") (pinfunction "B_5") (pintype "passive"))
    )
    (net (code "93") (name "Net-(U4C-W)") (class "Default")
      (node (ref "C51") (pin "2") (pinfunction "2_2") (pintype "passive"))
      (node (ref "U4") (pin "6") (pinfunction "W_6") (pintype "passive"))
    )
    (net (code "94") (name "Net-(U5B-A)") (class "Default")
      (node (ref "R14") (pin "1") (pinfunction "1_1") (pintype "passive"))
      (node (ref "U5") (pin "8") (pinfunction "A_8") (pintype "passive"))
    )
    (net (code "95") (name "Net-(U5B-B)") (class "Default")
      (node (ref "R15") (pin "2") (pinfunction "2_2") (pintype "passive"))
      (node (ref "U5") (pin "10") (pinfunction "B_10") (pintype "passive"))
    )
    (net (code "96") (name "Net-(U5B-W)") (class "Default")
      (node (ref "C25") (pin "2") (pinfunction "2_2") (pintype "passive"))
      (node (ref "U5") (pin "9") (pinfunction "W_9") (pintype "passive"))
    )
    (net (code "97") (name "Net-(U5C-A)") (class "Default")
      (node (ref "R37") (pin "1") (pinfunction "1_1") (pintype "passive"))
      (node (ref "U5") (pin "7") (pinfunction "A_7") (pintype "passive"))
    )
    (net (code "98") (name "Net-(U5C-B)") (class "Default")
      (node (ref "R38") (pin "2") (pinfunction "2_2") (pintype "passive"))
      (node (ref "U5") (pin "5") (pinfunction "B_5") (pintype "passive"))
    )
    (net (code "99") (name "Net-(U5C-W)") (class "Default")
      (node (ref "C59") (pin "2") (pinfunction "2_2") (pintype "passive"))
      (node (ref "U5") (pin "6") (pinfunction "W_6") (pintype "passive"))
    )
    (net (code "100") (name "Net-(U6-INNA)") (class "Default")
      (node (ref "C32") (pin "2") (pinfunction "2_2") (pintype "passive"))
      (node (ref "C33") (pin "2") (pinfunction "2_2") (pintype "passive"))
      (node (ref "U6") (pin "23") (pinfunction "INNA_23") (pintype "bidirectional"))
    )
    (net (code "101") (name "Net-(U6-INNB)") (class "Default")
      (node (ref "C40") (pin "2") (pinfunction "2_2") (pintype "passive"))
      (node (ref "C41") (pin "2") (pinfunction "2_2") (pintype "passive"))
      (node (ref "U6") (pin "33") (pinfunction "INNB_33") (pintype "bidirectional"))
    )
    (net (code "102") (name "Net-(U6-INPA)") (class "Default")
      (node (ref "C22") (pin "2") (pinfunction "2_2") (pintype "passive"))
      (node (ref "C27") (pin "2") (pinfunction "2_2") (pintype "passive"))
      (node (ref "U6") (pin "22") (pinfunction "INPA_22") (pintype "bidirectional"))
    )
    (net (code "103") (name "Net-(U6-INPB)") (class "Default")
      (node (ref "C37") (pin "2") (pinfunction "2_2") (pintype "passive"))
      (node (ref "C39") (pin "2") (pinfunction "2_2") (pintype "passive"))
      (node (ref "U6") (pin "32") (pinfunction "INPB_32") (pintype "bidirectional"))
    )
    (net (code "104") (name "Net-(U6-MUTE)") (class "Default")
      (node (ref "R54") (pin "1") (pinfunction "1_1") (pintype "passive"))
      (node (ref "U6") (pin "21") (pinfunction "MUTE_21") (pintype "bidirectional"))
    )
    (net (code "105") (name "Net-(U6-PGND)") (class "Default")
      (node (ref "C49") (pin "2") (pinfunction "2_2") (pintype "passive"))
      (node (ref "U6") (pin "18") (pinfunction "PGND_18") (pintype "bidirectional"))
    )
    (net (code "106") (name "Net-(U6-ROSC)") (class "Default")
      (node (ref "C58") (pin "1") (pinfunction "1_1") (pintype "passive"))
      (node (ref "R41") (pin "2") (pinfunction "2_2") (pintype "passive"))
      (node (ref "U6") (pin "24") (pinfunction "ROSC_24") (pintype "bidirectional"))
    )
    (net (code "107") (name "Net-(U6-STBY)") (class "Default")
      (node (ref "R55") (pin "1") (pinfunction "1_1") (pintype "passive"))
      (node (ref "U6") (pin "20") (pinfunction "STBY_20") (pintype "bidirectional"))
    )
    (net (code "108") (name "Net-(U6-SVCC)") (class "Default")
      (node (ref "C52") (pin "1") (pinfunction "1_1") (pintype "passive"))
      (node (ref "U6") (pin "35") (pinfunction "SVCC_35") (pintype "bidirectional"))
    )
    (net (code "109") (name "Net-(U6-SVR)") (class "Default")
      (node (ref "C61") (pin "+") (pinfunction "+_+") (pintype "passive"))
      (node (ref "U6") (pin "29") (pinfunction "SVR_29") (pintype "bidirectional"))
    )
    (net (code "110") (name "Net-(U6-VDDPW)") (class "Default")
      (node (ref "C49") (pin "1") (pinfunction "1_1") (pintype "passive"))
      (node (ref "R27") (pin "1") (pinfunction "1_1") (pintype "passive"))
      (node (ref "U6") (pin "19") (pinfunction "VDDPW_19") (pintype "bidirectional"))
    )
    (net (code "111") (name "Net-(U6-VREF)") (class "Default")
      (node (ref "C60") (pin "+") (pinfunction "+_+") (pintype "passive"))
      (node (ref "U6") (pin "34") (pinfunction "VREF_34") (pintype "bidirectional"))
    )
    (net (code "112") (name "Net-(U6-VSS)") (class "Default")
      (node (ref "C52") (pin "2") (pinfunction "2_2") (pintype "passive"))
      (node (ref "U6") (pin "36") (pinfunction "VSS_36") (pintype "bidirectional"))
    )
    (net (code "113") (name "Net-(U7B-B)") (class "Default")
      (node (ref "U7") (pin "10") (pinfunction "B_10") (pintype "passive"))
      (node (ref "X1") (pin "5") (pinfunction "T1_5") (pintype "passive"))
    )
    (net (code "114") (name "Net-(U7B-W)") (class "Default")
      (node (ref "R35") (pin "1") (pinfunction "1_1") (pintype "passive"))
      (node (ref "U7") (pin "9") (pinfunction "W_9") (pintype "passive"))
    )
    (net (code "115") (name "Net-(U7C-B)") (class "Default")
      (node (ref "U7") (pin "5") (pinfunction "B_5") (pintype "passive"))
      (node (ref "X1") (pin "6") (pinfunction "T2_6") (pintype "passive"))
    )
    (net (code "116") (name "Net-(U7C-W)") (class "Default")
      (node (ref "R28") (pin "1") (pinfunction "1_1") (pintype "passive"))
      (node (ref "U7") (pin "6") (pinfunction "W_6") (pintype "passive"))
    )
    (net (code "117") (name "Net-(U8B-B)") (class "Default")
      (node (ref "U8") (pin "10") (pinfunction "B_10") (pintype "passive"))
      (node (ref "X1") (pin "2") (pinfunction "T1_2") (pintype "passive"))
    )
    (net (code "118") (name "Net-(U8B-W)") (class "Default")
      (node (ref "R19") (pin "1") (pinfunction "1_1") (pintype "passive"))
      (node (ref "U8") (pin "9") (pinfunction "W_9") (pintype "passive"))
    )
    (net (code "119") (name "Net-(U8C-B)") (class "Default")
      (node (ref "U8") (pin "5") (pinfunction "B_5") (pintype "passive"))
      (node (ref "X1") (pin "3") (pinfunction "T2_3") (pintype "passive"))
    )
    (net (code "120") (name "Net-(U8C-W)") (class "Default")
      (node (ref "R11") (pin "1") (pinfunction "1_1") (pintype "passive"))
      (node (ref "U8") (pin "6") (pinfunction "W_6") (pintype "passive"))
    )
    (net (code "121") (name "PE") (class "Default")
      (node (ref "H1") (pin "B3,0") (pinfunction "MOUNT_B3,0") (pintype "passive"))
      (node (ref "H2") (pin "B3,0") (pinfunction "MOUNT_B3,0") (pintype "passive"))
      (node (ref "H3") (pin "B3,0") (pinfunction "MOUNT_B3,0") (pintype "passive"))
      (node (ref "H4") (pin "B3,0") (pinfunction "MOUNT_B3,0") (pintype "passive"))
      (node (ref "J4") (pin "P$1") (pinfunction "P$1_P$1") (pintype "bidirectional"))
      (node (ref "J4") (pin "P$2") (pinfunction "P$1_P$2") (pintype "bidirectional"))
      (node (ref "J9") (pin "S1") (pinfunction "SHIELD_S1") (pintype "bidirectional"))
      (node (ref "J9") (pin "S2") (pinfunction "SHIELD_S2") (pintype "bidirectional"))
      (node (ref "J9") (pin "S3") (pinfunction "SHIELD_S3") (pintype "bidirectional"))
      (node (ref "J9") (pin "S4") (pinfunction "SHIELD_S4") (pintype "bidirectional"))
      (node (ref "JP10") (pin "2") (pinfunction "2_2") (pintype "passive"))
      (node (ref "U6") (pin "1") (pinfunction "SUB_GND_1") (pintype "bidirectional"))
    )
    (net (code "122") (name "POWER_LED") (class "Default")
      (node (ref "IC6") (pin "14") (pinfunction "PB2(SS/OC1B)_14") (pintype "bidirectional"))
      (node (ref "X4") (pin "2") (pinfunction "2_2") (pintype "passive"))
    )
    (net (code "123") (name "PWR_BTN") (class "Default")
      (node (ref "IC6") (pin "1") (pinfunction "PD3(INT1)_1") (pintype "bidirectional"))
      (node (ref "X2") (pin "2") (pinfunction "2_2") (pintype "passive"))
    )
    (net (code "124") (name "R_OUT+") (class "Default")
      (node (ref "C30") (pin "1") (pinfunction "1_1") (pintype "passive"))
      (node (ref "C35") (pin "1") (pinfunction "1_1") (pintype "passive"))
      (node (ref "K2") (pin "S2") (pinfunction "S_S2") (pintype "passive"))
      (node (ref "L1") (pin "2") (pinfunction "2_2") (pintype "passive"))
      (node (ref "R16") (pin "2") (pinfunction "2_2") (pintype "passive"))
    )
    (net (code "125") (name "R_OUT-") (class "Default")
      (node (ref "C35") (pin "2") (pinfunction "2_2") (pintype "passive"))
      (node (ref "C36") (pin "2") (pinfunction "2_2") (pintype "passive"))
      (node (ref "J5") (pin "2") (pinfunction "P$1_2") (pintype "bidirectional"))
      (node (ref "L2") (pin "2") (pinfunction "2_2") (pintype "passive"))
      (node (ref "R22") (pin "1") (pinfunction "1_1") (pintype "passive"))
    )
    (net (code "126") (name "SCL") (class "Default")
      (node (ref "IC6") (pin "28") (pinfunction "PC5(ADC5/SCL)_28") (pintype "bidirectional"))
      (node (ref "J8") (pin "4") (pinfunction "4_4") (pintype "passive"))
      (node (ref "R52") (pin "1") (pinfunction "1_1") (pintype "passive"))
      (node (ref "U2") (pin "2") (pinfunction "SCL_2") (pintype "bidirectional"))
      (node (ref "U3") (pin "2") (pinfunction "SCL_2") (pintype "bidirectional"))
      (node (ref "U4") (pin "2") (pinfunction "SCL_2") (pintype "bidirectional"))
      (node (ref "U5") (pin "2") (pinfunction "SCL_2") (pintype "bidirectional"))
      (node (ref "U7") (pin "2") (pinfunction "SCL_2") (pintype "bidirectional"))
      (node (ref "U8") (pin "2") (pinfunction "SCL_2") (pintype "bidirectional"))
    )
    (net (code "127") (name "SDA") (class "Default")
      (node (ref "IC6") (pin "27") (pinfunction "PC4(ADC4/SDA)_27") (pintype "bidirectional"))
      (node (ref "J8") (pin "3") (pinfunction "3_3") (pintype "passive"))
      (node (ref "R2") (pin "1") (pinfunction "1_1") (pintype "passive"))
      (node (ref "U2") (pin "3") (pinfunction "SDA_3") (pintype "bidirectional"))
      (node (ref "U3") (pin "3") (pinfunction "SDA_3") (pintype "bidirectional"))
      (node (ref "U4") (pin "3") (pinfunction "SDA_3") (pintype "bidirectional"))
      (node (ref "U5") (pin "3") (pinfunction "SDA_3") (pintype "bidirectional"))
      (node (ref "U7") (pin "3") (pinfunction "SDA_3") (pintype "bidirectional"))
      (node (ref "U8") (pin "3") (pinfunction "SDA_3") (pintype "bidirectional"))
    )
    (net (code "128") (name "SPK_PROTECT") (class "Default")
      (node (ref "IC6") (pin "11") (pinfunction "PD7(AIN1)_11") (pintype "bidirectional"))
      (node (ref "T2") (pin "B") (pinfunction "B_B") (pintype "passive"))
    )
    (net (code "129") (name "T_SENSE") (class "Default")
      (node (ref "IC6") (pin "24") (pinfunction "PC1(ADC1)_24") (pintype "bidirectional"))
      (node (ref "U9") (pin "2") (pinfunction "VO_2") (pintype "bidirectional"))
    )
    (net (code "130") (name "VDD") (class "Default")
      (node (ref "C62") (pin "2") (pinfunction "2_2") (pintype "passive"))
      (node (ref "R27") (pin "2") (pinfunction "2_2") (pintype "passive"))
      (node (ref "U6") (pin "26") (pinfunction "VDDS_26") (pintype "bidirectional"))
    )
    (net (code "131") (name "VPP") (class "Default")
      (node (ref "D12") (pin "A") (pinfunction "A_A") (pintype "passive"))
      (node (ref "X3") (pin "2") (pinfunction "S_2") (pintype "passive"))
    )
    (net (code "132") (name "unconnected-(IC6-ADC6-Pad19)") (class "Default")
      (node (ref "IC6") (pin "19") (pinfunction "ADC6_19") (pintype "bidirectional"))
    )
    (net (code "133") (name "unconnected-(IC6-ADC7-Pad22)") (class "Default")
      (node (ref "IC6") (pin "22") (pinfunction "ADC7_22") (pintype "bidirectional"))
    )
    (net (code "134") (name "unconnected-(IC6-PB6(XTAL1{slash}TOSC1)-Pad7)") (class "Default")
      (node (ref "IC6") (pin "7") (pinfunction "PB6(XTAL1/TOSC1)_7") (pintype "bidirectional"))
    )
    (net (code "135") (name "unconnected-(IC6-PB7(XTAL2{slash}TOSC2)-Pad8)") (class "Default")
      (node (ref "IC6") (pin "8") (pinfunction "PB7(XTAL2/TOSC2)_8") (pintype "bidirectional"))
    )
    (net (code "136") (name "unconnected-(IC6-PC3(ADC3)-Pad26)") (class "Default")
      (node (ref "IC6") (pin "26") (pinfunction "PC3(ADC3)_26") (pintype "bidirectional"))
    )
    (net (code "137") (name "unconnected-(J9-PadD+)") (class "Default")
      (node (ref "J9") (pin "D+") (pinfunction "D+_D+") (pintype "bidirectional"))
    )
    (net (code "138") (name "unconnected-(J9-PadD-)") (class "Default")
      (node (ref "J9") (pin "D-") (pinfunction "D-_D-") (pintype "bidirectional"))
    )
    (net (code "139") (name "unconnected-(K2B-O-PadO1)") (class "Default")
      (node (ref "K2") (pin "O1") (pinfunction "O_O1") (pintype "passive"))
    )
    (net (code "140") (name "unconnected-(K2C-O-PadO2)") (class "Default")
      (node (ref "K2") (pin "O2") (pinfunction "O_O2") (pintype "passive"))
    )
    (net (code "141") (name "unconnected-(U6-SYNCLK-Pad25)") (class "Default")
      (node (ref "U6") (pin "25") (pinfunction "SYNCLK_25") (pintype "bidirectional"))
    )
  )
)
